# ThrusterShieldV1_1.net
KiCad netlist of a schematic drawn in EAGLE
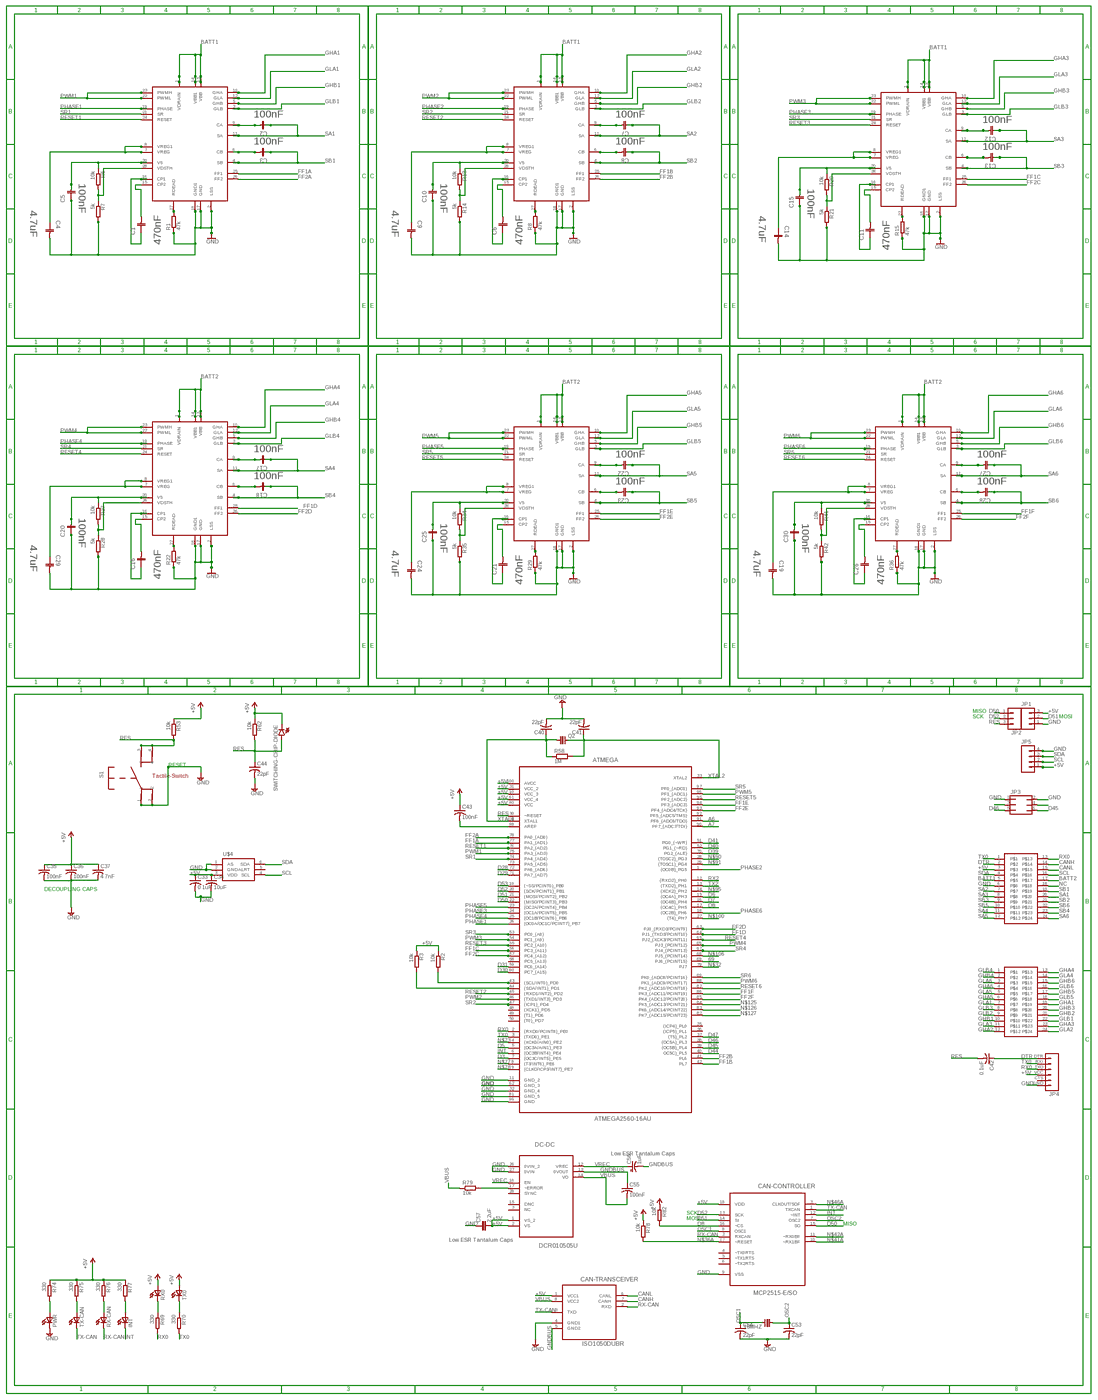
[diagram p0: schematic, sheet 1, overview]
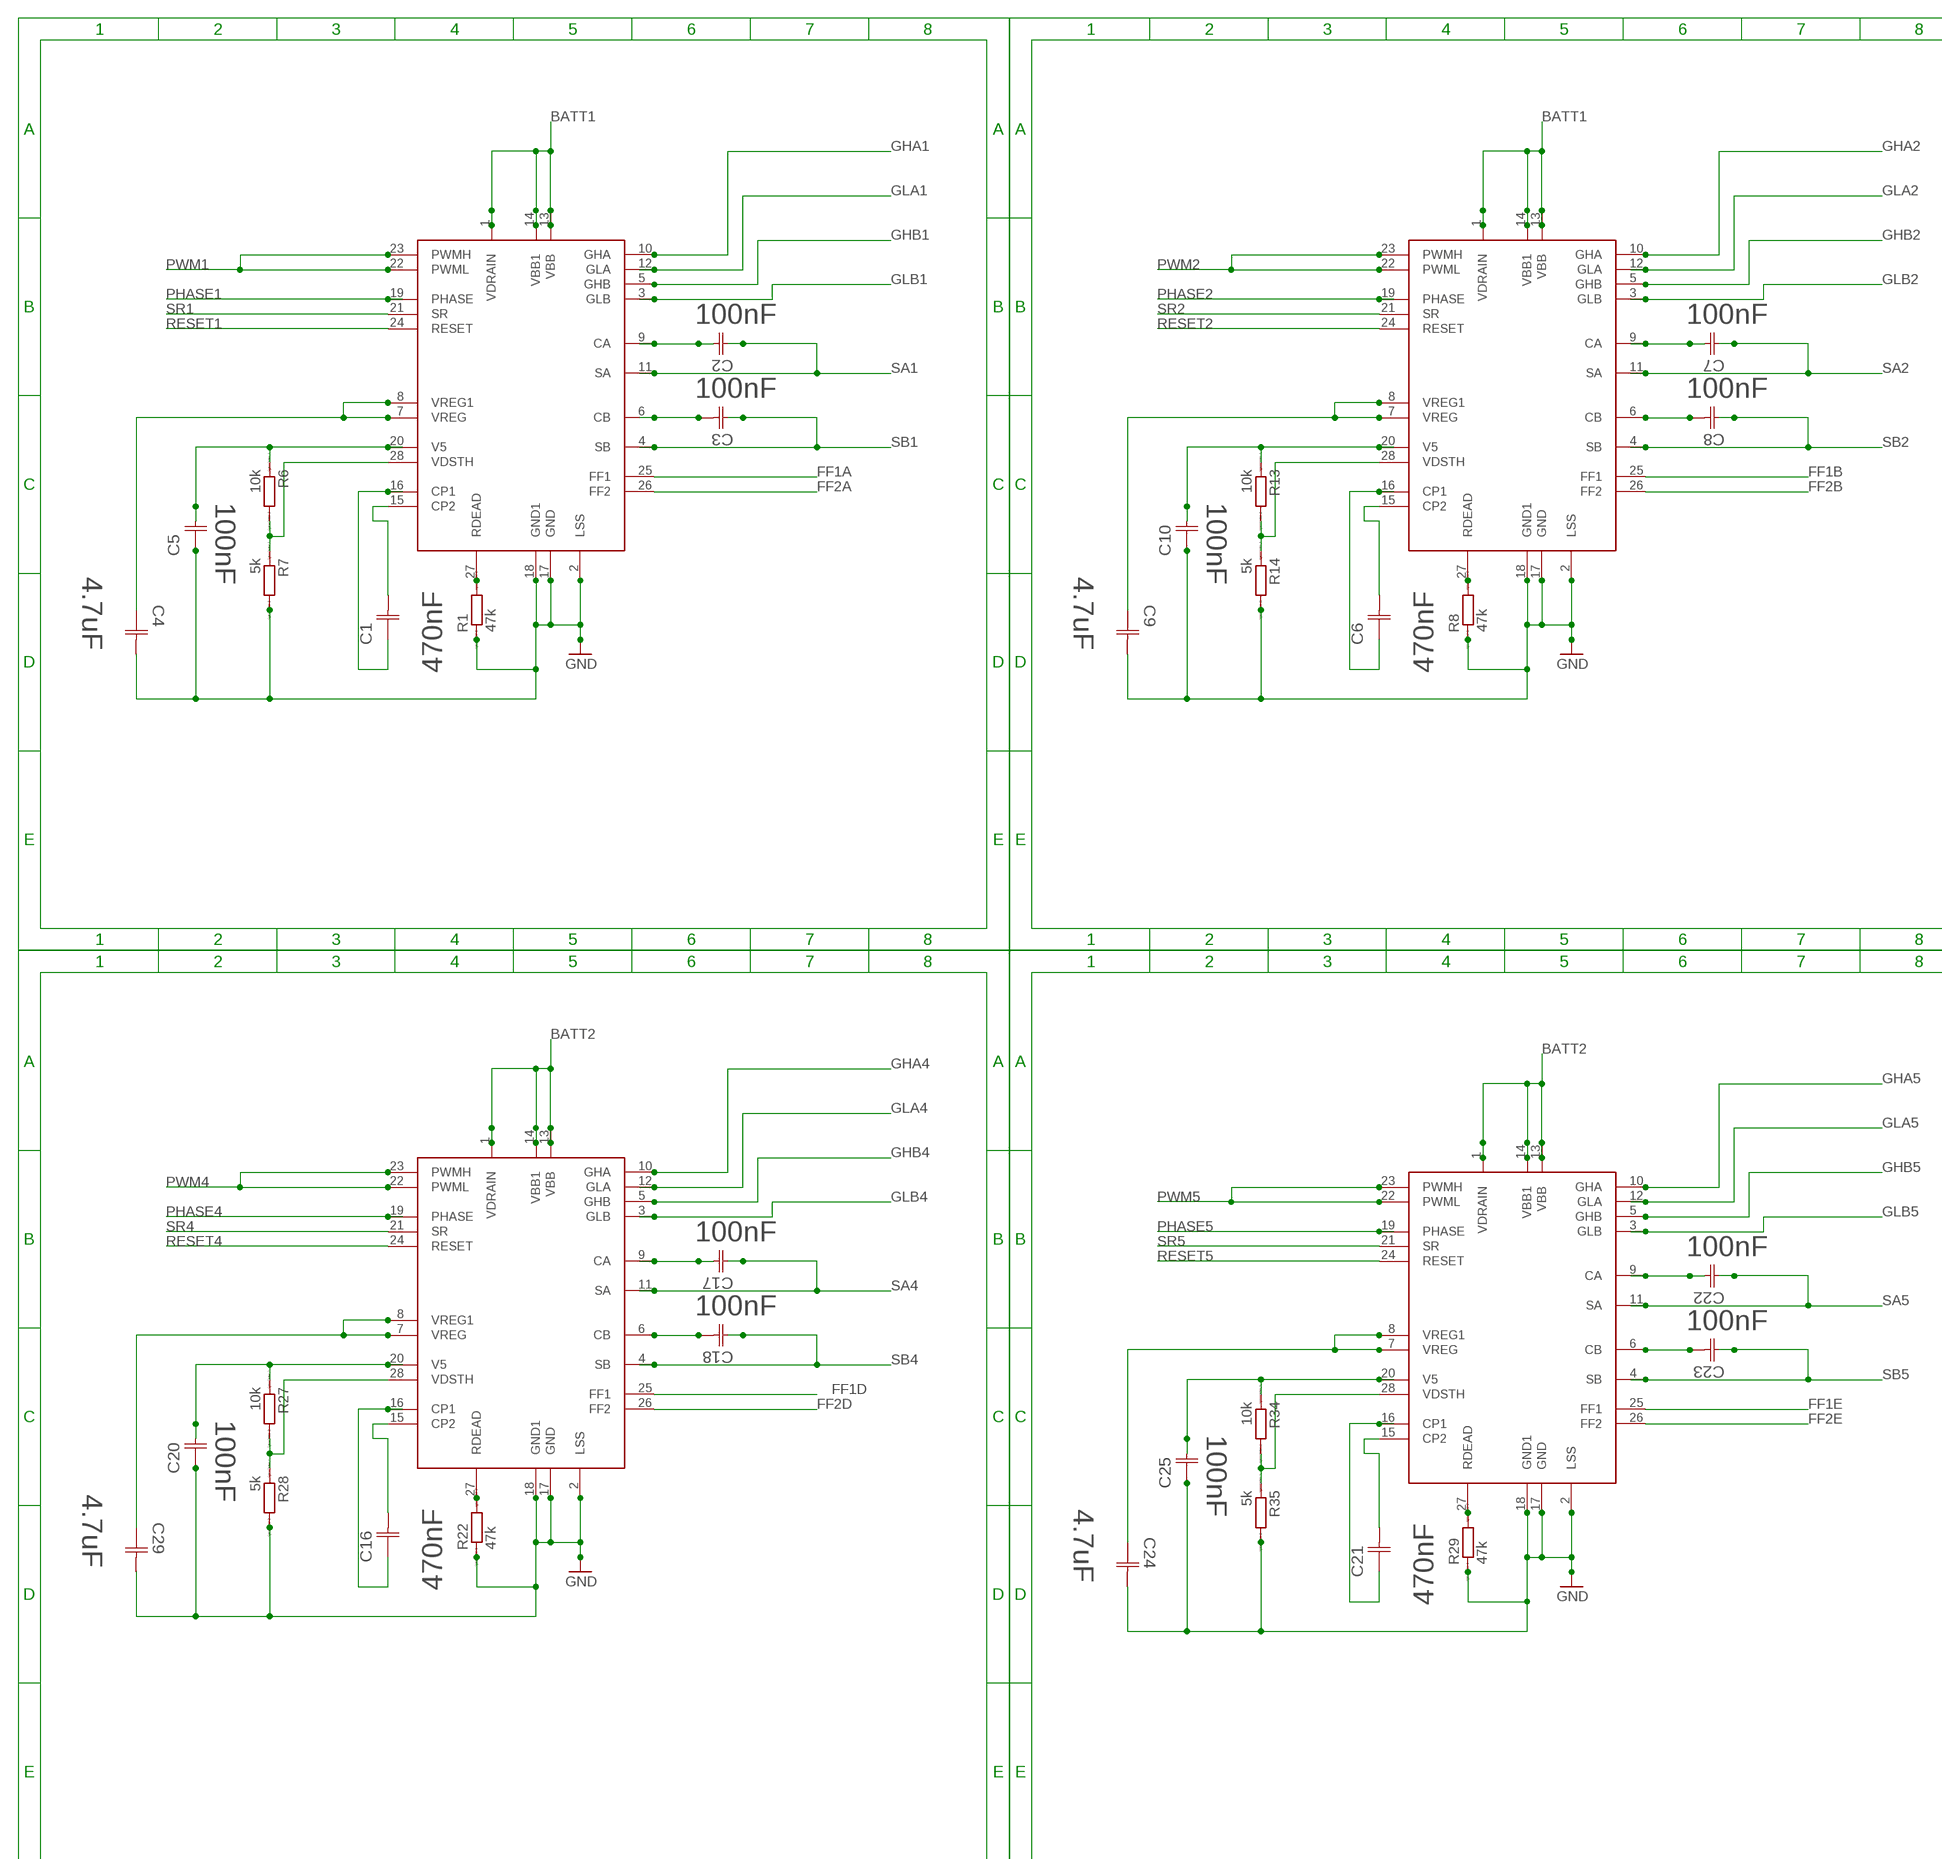
[diagram p1: schematic, sheet 1, part 1 of 4]
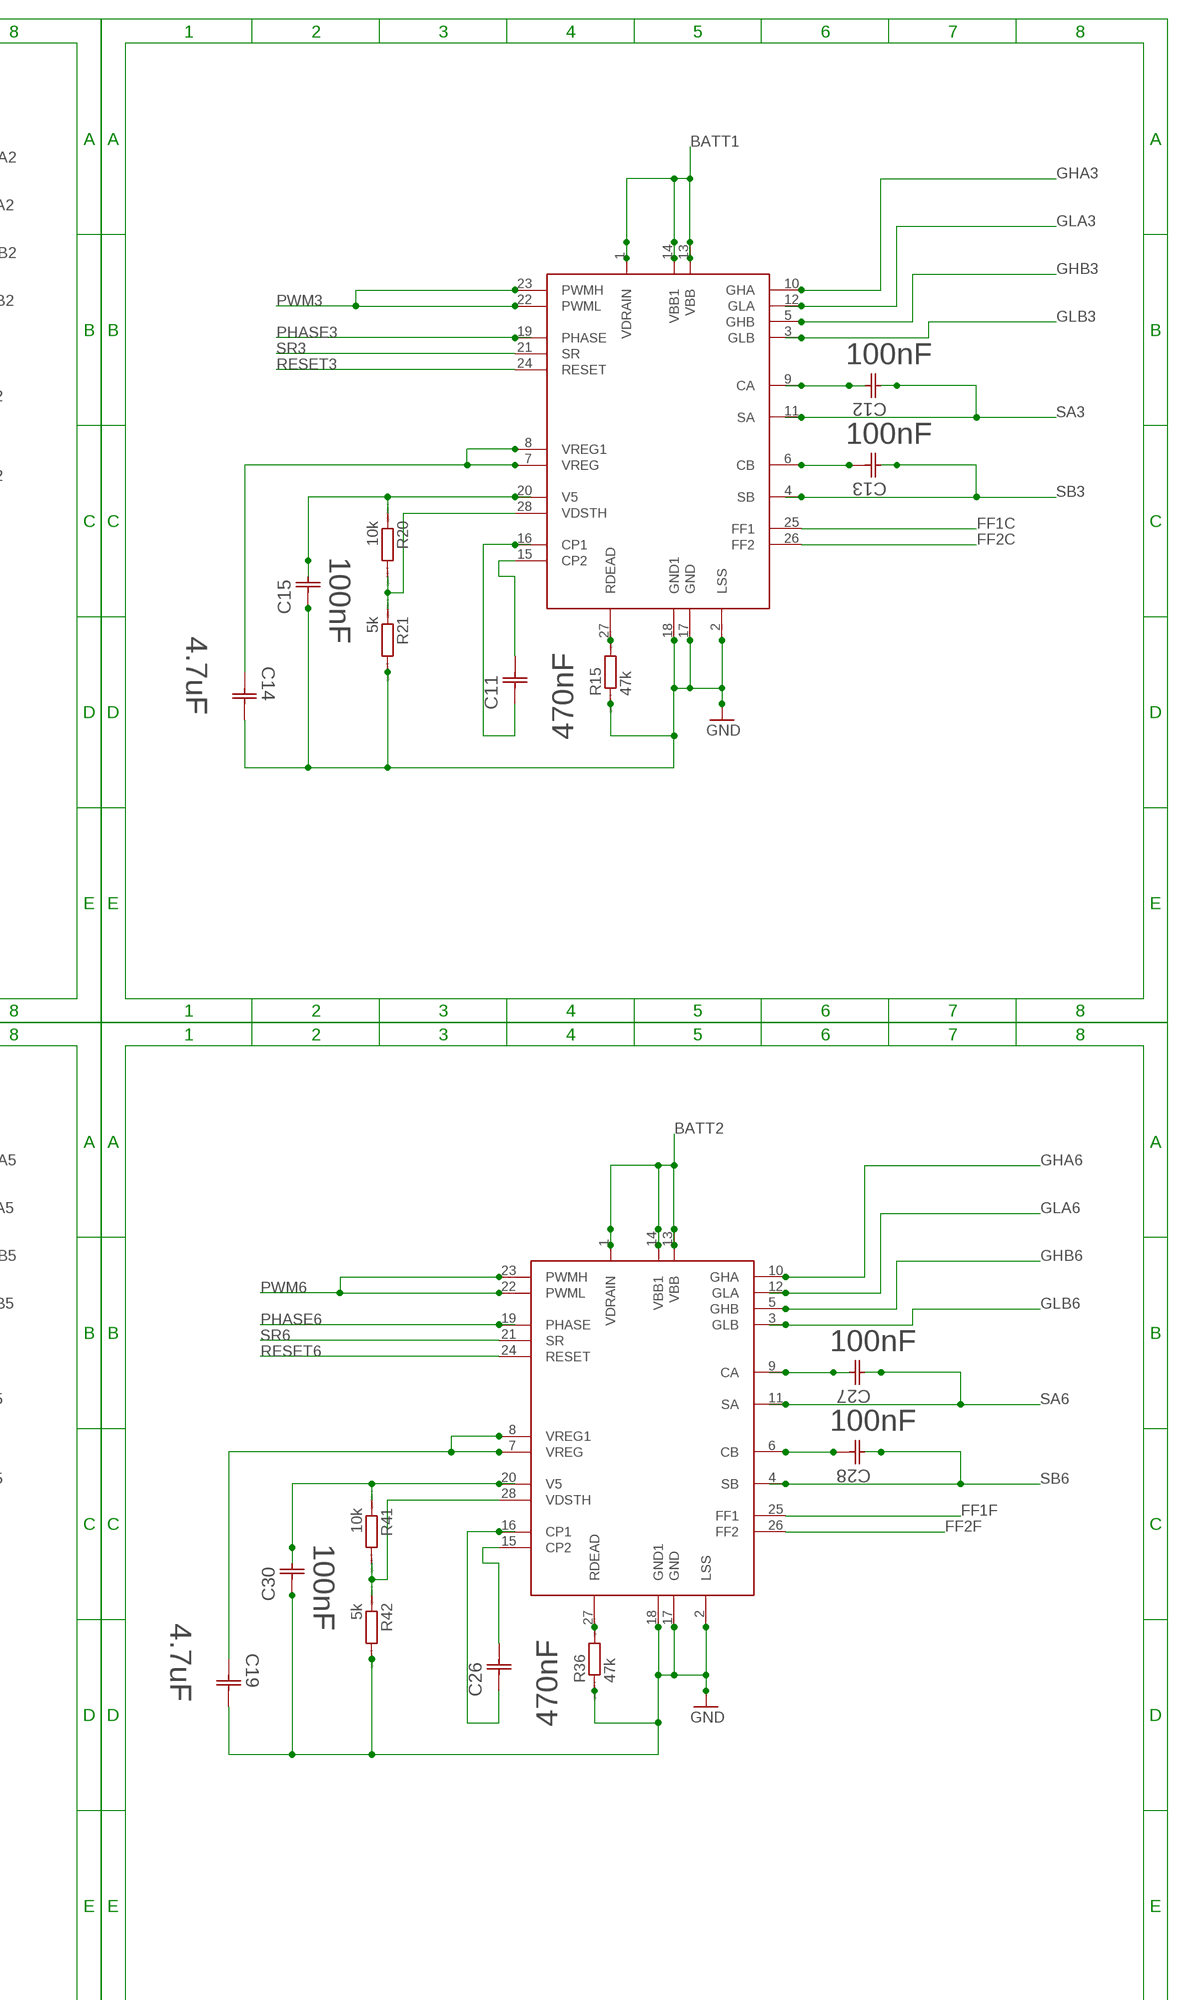
[diagram p2: schematic, sheet 1, part 2 of 4]
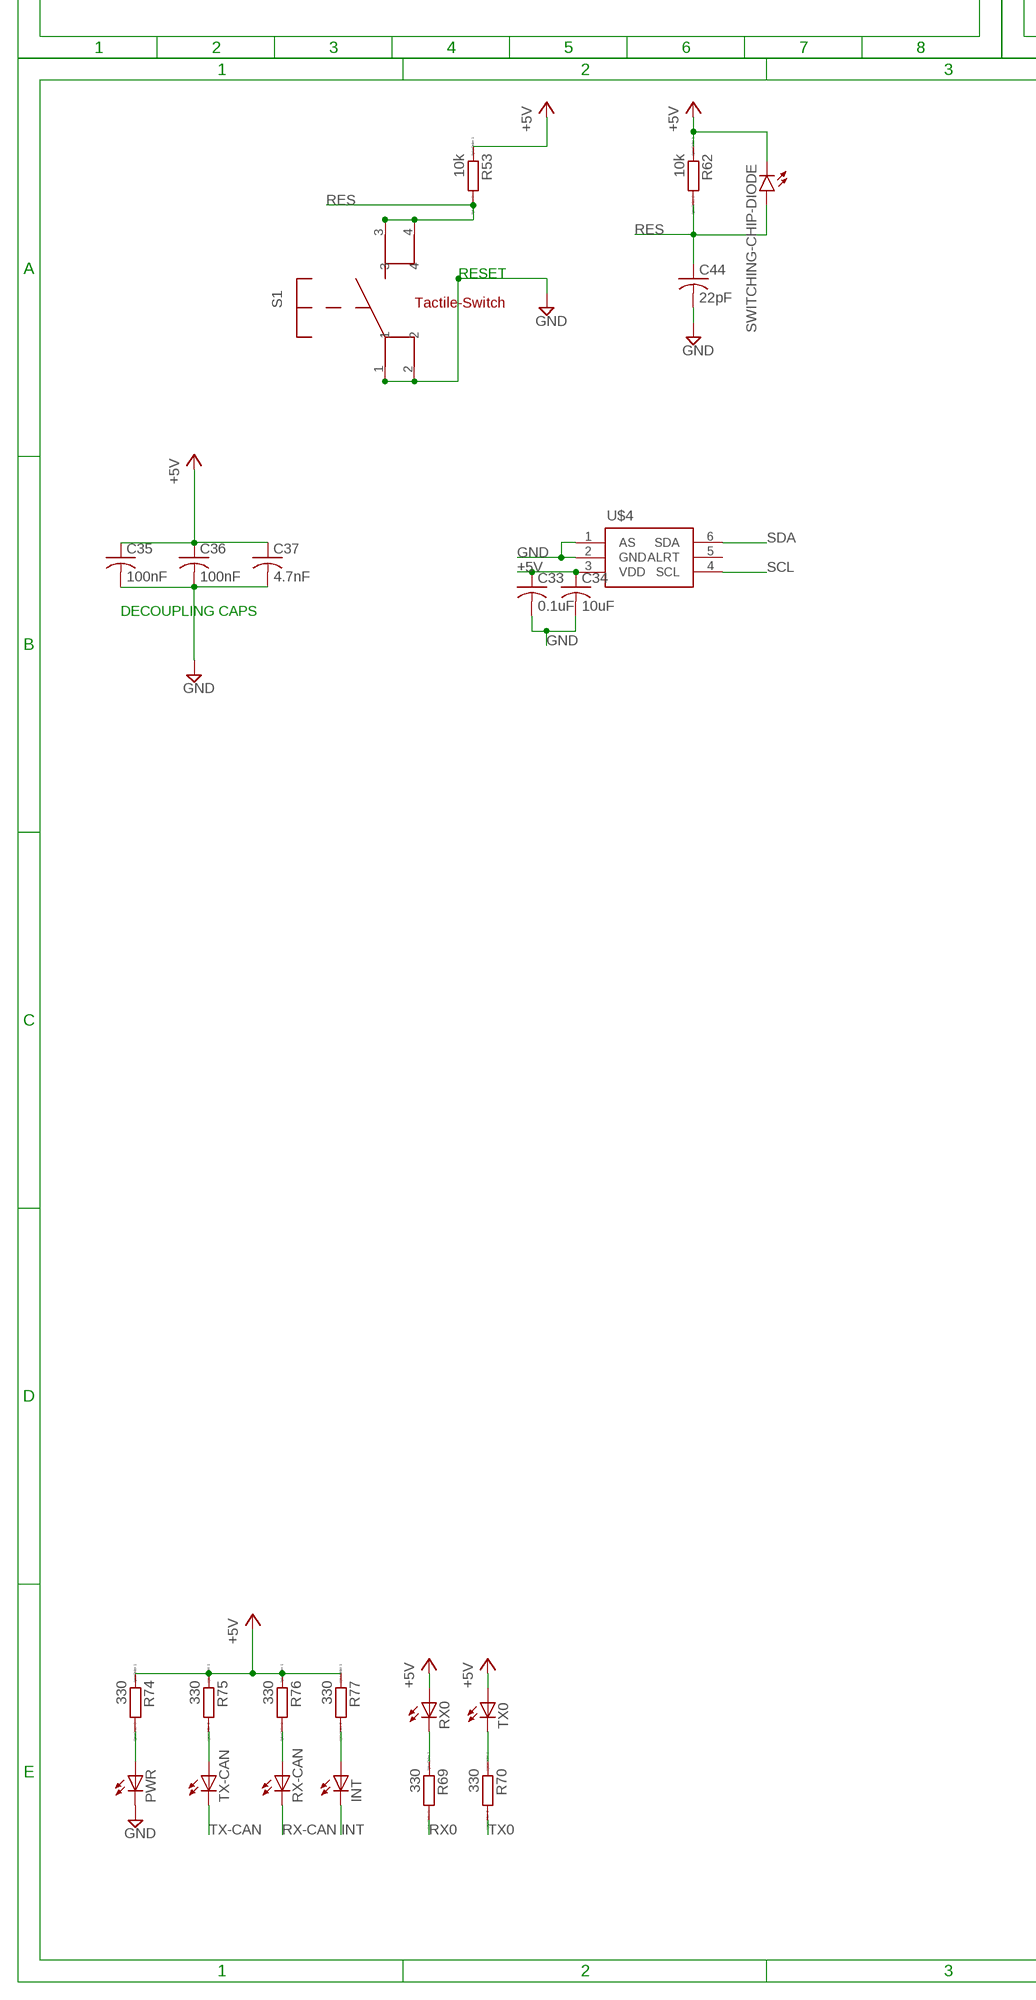
[diagram p3: schematic, sheet 1, part 3 of 4]
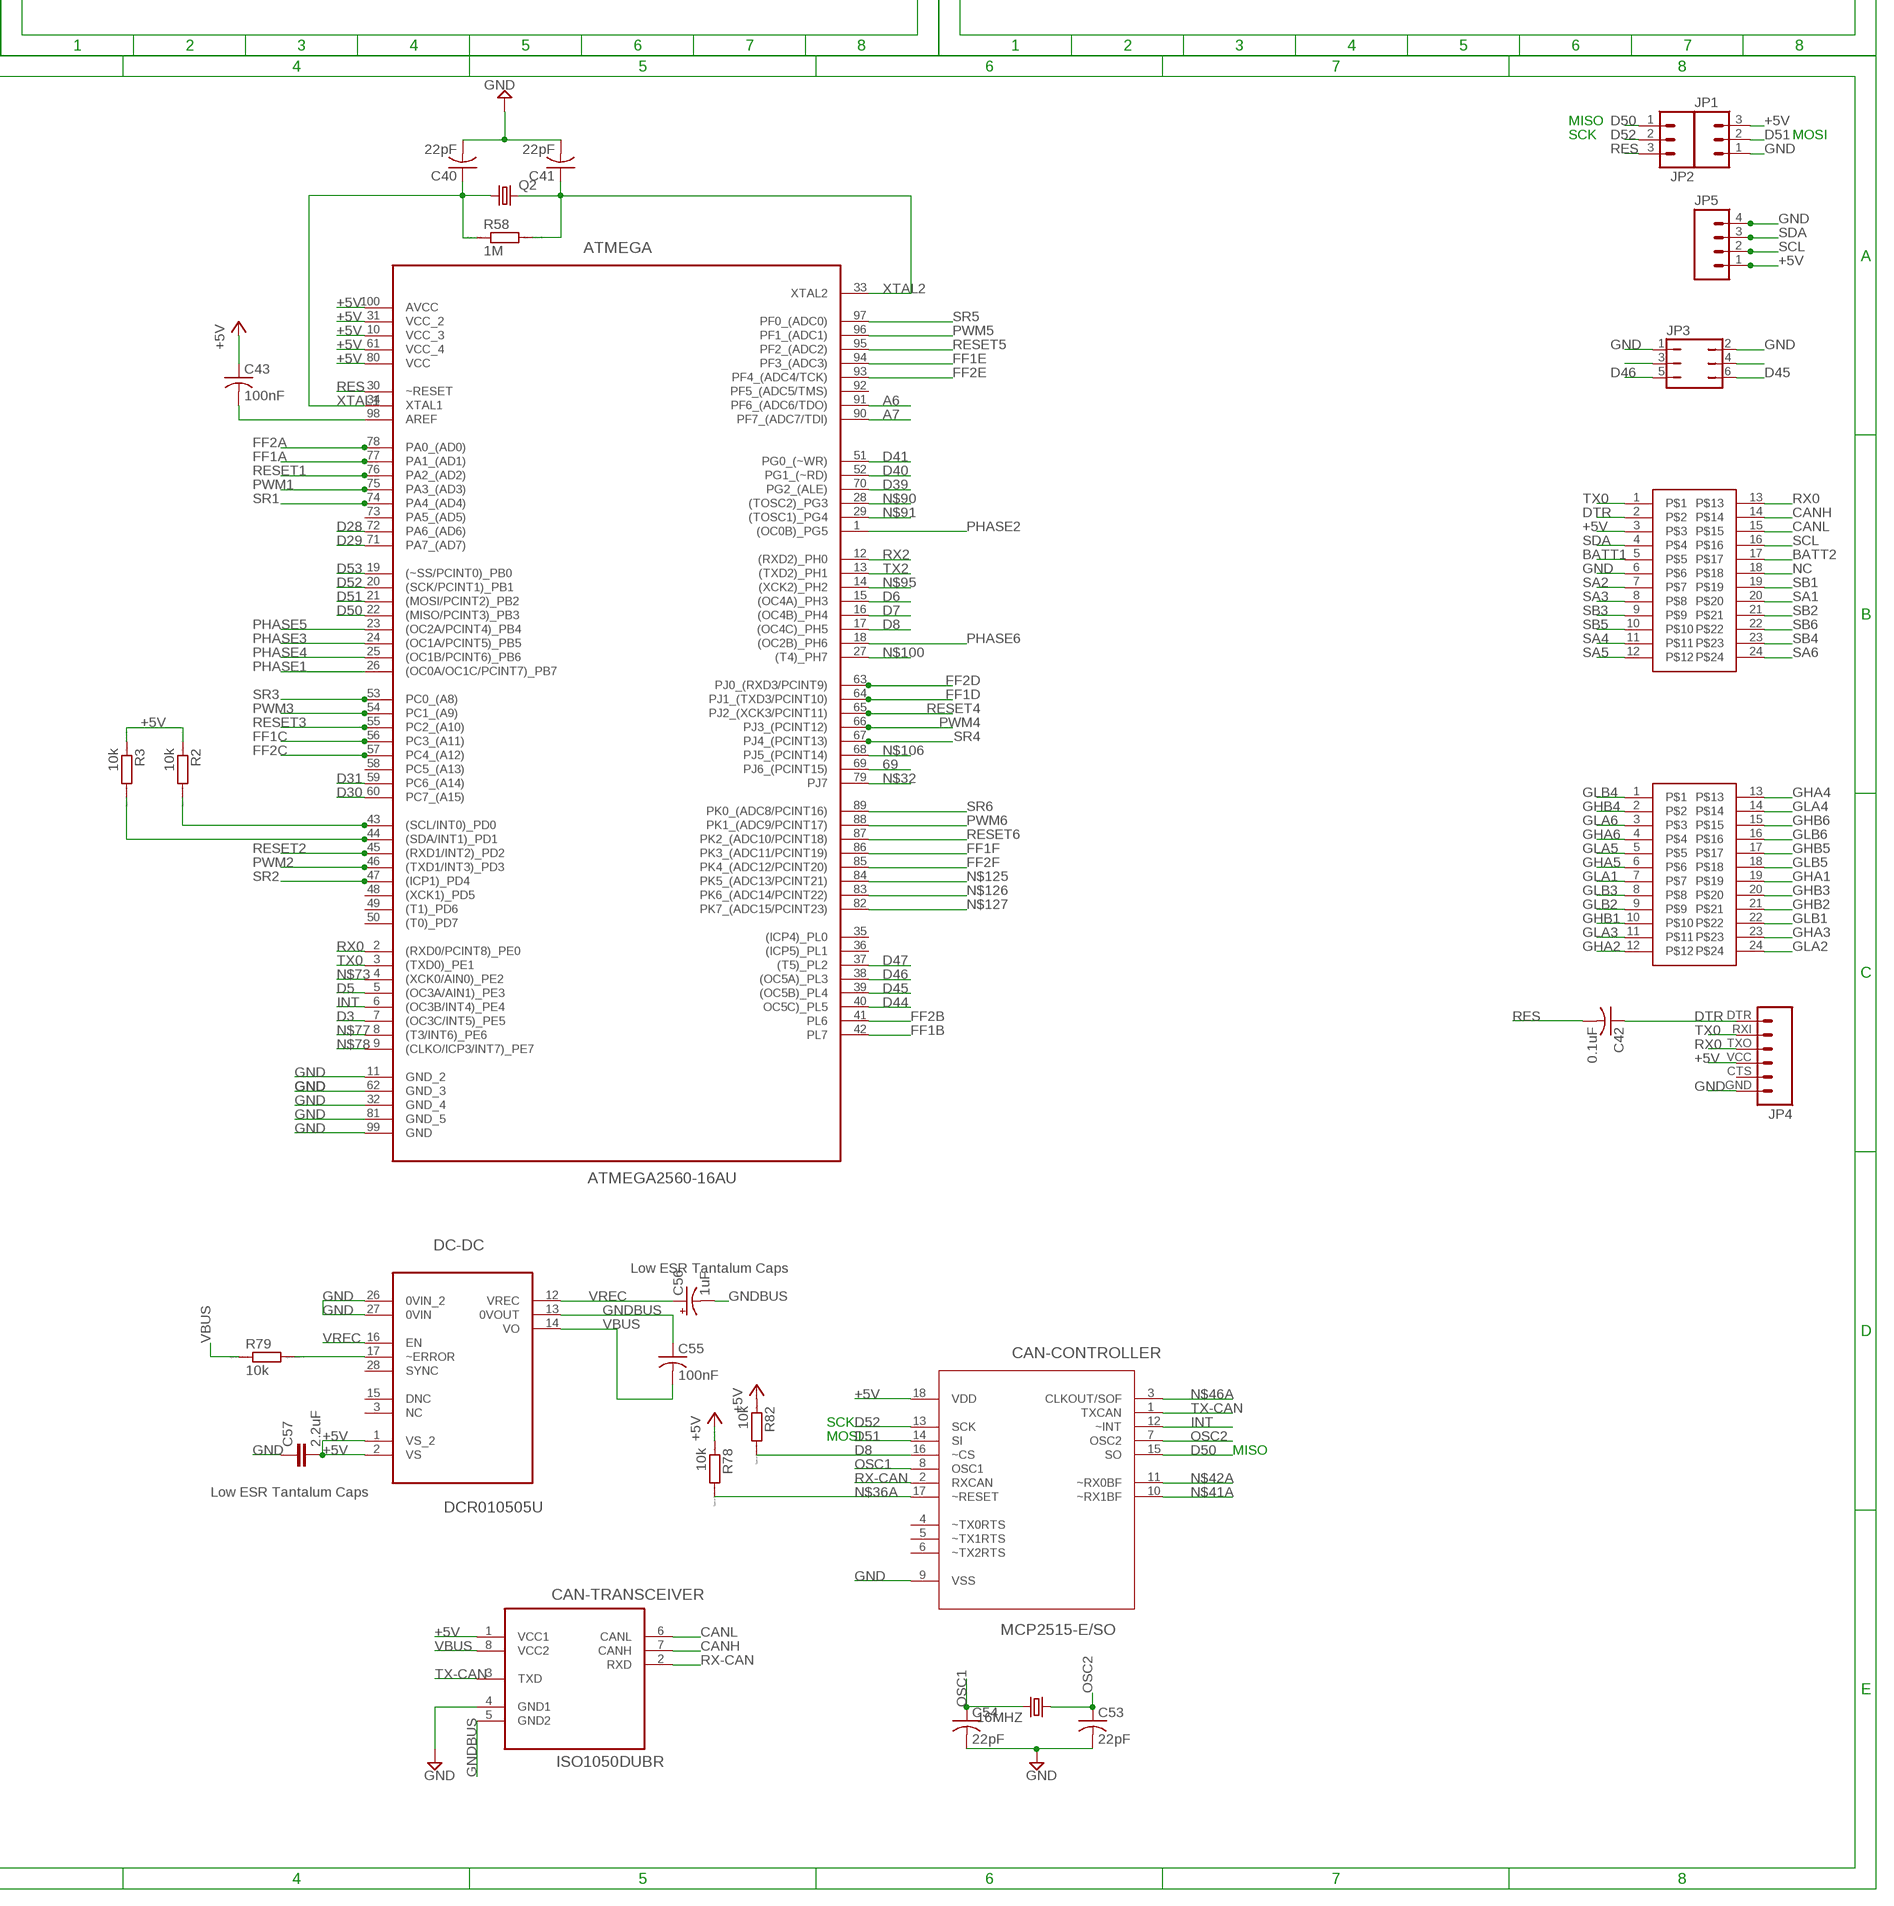
[diagram p4: schematic, sheet 1, part 4 of 4]

(export (version "E")
  (design (tool "Eeschema 10.0.6"))
  (components
    (comp (ref "16MHZ")
      (value "CRYSTALHC49UP")
      (footprint "eagle-import:HC49UP")
      (libsource (lib "eagle-import") (part "CRYSTALHC49UP"))
    )
    (comp (ref "ATMEGA")
      (value "ATMEGA2560-16AU")
      (footprint "eagle-import:QFP50P1600X1600X120-100N")
      (libsource (lib "eagle-import") (part "ATMEGA2560-16AU"))
    )
    (comp (ref "C1")
      (value "470nF")
      (footprint "eagle-import:CAPC2013X70N")
      (fields (field (name "MPN") "B37940K5100J60") (field (name "TOLERANCE") "±5%"))
      (libsource (lib "eagle-import") (part "B37940K5100J60"))
    )
    (comp (ref "C2")
      (value "100nF")
      (footprint "eagle-import:CAPC2013X70N")
      (fields (field (name "MPN") "B37940K5100J60") (field (name "TOLERANCE") "±5%"))
      (libsource (lib "eagle-import") (part "B37940K5100J60"))
    )
    (comp (ref "C3")
      (value "100nF")
      (footprint "eagle-import:CAPC2013X70N")
      (fields (field (name "MPN") "B37940K5100J60") (field (name "TOLERANCE") "±5%"))
      (libsource (lib "eagle-import") (part "B37940K5100J60"))
    )
    (comp (ref "C4")
      (value "4.7uF")
      (footprint "eagle-import:CAPC2013X70N")
      (fields (field (name "MPN") "B37940K5100J60") (field (name "TOLERANCE") "±5%"))
      (libsource (lib "eagle-import") (part "B37940K5100J60"))
    )
    (comp (ref "C5")
      (value "100nF")
      (footprint "eagle-import:CAPC2013X70N")
      (fields (field (name "MPN") "B37940K5100J60") (field (name "TOLERANCE") "±5%"))
      (libsource (lib "eagle-import") (part "B37940K5100J60"))
    )
    (comp (ref "C6")
      (value "470nF")
      (footprint "eagle-import:CAPC2013X70N")
      (fields (field (name "MPN") "B37940K5100J60") (field (name "TOLERANCE") "±5%"))
      (libsource (lib "eagle-import") (part "B37940K5100J60"))
    )
    (comp (ref "C7")
      (value "100nF")
      (footprint "eagle-import:CAPC2013X70N")
      (fields (field (name "MPN") "B37940K5100J60") (field (name "TOLERANCE") "±5%"))
      (libsource (lib "eagle-import") (part "B37940K5100J60"))
    )
    (comp (ref "C8")
      (value "100nF")
      (footprint "eagle-import:CAPC2013X70N")
      (fields (field (name "MPN") "B37940K5100J60") (field (name "TOLERANCE") "±5%"))
      (libsource (lib "eagle-import") (part "B37940K5100J60"))
    )
    (comp (ref "C9")
      (value "4.7uF")
      (footprint "eagle-import:CAPC2013X70N")
      (fields (field (name "MPN") "B37940K5100J60") (field (name "TOLERANCE") "±5%"))
      (libsource (lib "eagle-import") (part "B37940K5100J60"))
    )
    (comp (ref "C10")
      (value "100nF")
      (footprint "eagle-import:CAPC2013X70N")
      (fields (field (name "MPN") "B37940K5100J60") (field (name "TOLERANCE") "±5%"))
      (libsource (lib "eagle-import") (part "B37940K5100J60"))
    )
    (comp (ref "C11")
      (value "470nF")
      (footprint "eagle-import:CAPC2013X70N")
      (fields (field (name "MPN") "B37940K5100J60") (field (name "TOLERANCE") "±5%"))
      (libsource (lib "eagle-import") (part "B37940K5100J60"))
    )
    (comp (ref "C12")
      (value "100nF")
      (footprint "eagle-import:CAPC2013X70N")
      (fields (field (name "MPN") "B37940K5100J60") (field (name "TOLERANCE") "±5%"))
      (libsource (lib "eagle-import") (part "B37940K5100J60"))
    )
    (comp (ref "C13")
      (value "100nF")
      (footprint "eagle-import:CAPC2013X70N")
      (fields (field (name "MPN") "B37940K5100J60") (field (name "TOLERANCE") "±5%"))
      (libsource (lib "eagle-import") (part "B37940K5100J60"))
    )
    (comp (ref "C14")
      (value "4.7uF")
      (footprint "eagle-import:CAPC2013X70N")
      (fields (field (name "MPN") "B37940K5100J60") (field (name "TOLERANCE") "±5%"))
      (libsource (lib "eagle-import") (part "B37940K5100J60"))
    )
    (comp (ref "C15")
      (value "100nF")
      (footprint "eagle-import:CAPC2013X70N")
      (fields (field (name "MPN") "B37940K5100J60") (field (name "TOLERANCE") "±5%"))
      (libsource (lib "eagle-import") (part "B37940K5100J60"))
    )
    (comp (ref "C16")
      (value "470nF")
      (footprint "eagle-import:CAPC2013X70N")
      (fields (field (name "MPN") "B37940K5100J60") (field (name "TOLERANCE") "±5%"))
      (libsource (lib "eagle-import") (part "B37940K5100J60"))
    )
    (comp (ref "C17")
      (value "100nF")
      (footprint "eagle-import:CAPC2013X70N")
      (fields (field (name "MPN") "B37940K5100J60") (field (name "TOLERANCE") "±5%"))
      (libsource (lib "eagle-import") (part "B37940K5100J60"))
    )
    (comp (ref "C18")
      (value "100nF")
      (footprint "eagle-import:CAPC2013X70N")
      (fields (field (name "MPN") "B37940K5100J60") (field (name "TOLERANCE") "±5%"))
      (libsource (lib "eagle-import") (part "B37940K5100J60"))
    )
    (comp (ref "C19")
      (value "4.7uF")
      (footprint "eagle-import:CAPC2013X70N")
      (fields (field (name "MPN") "B37940K5100J60") (field (name "TOLERANCE") "±5%"))
      (libsource (lib "eagle-import") (part "B37940K5100J60"))
    )
    (comp (ref "C20")
      (value "100nF")
      (footprint "eagle-import:CAPC2013X70N")
      (fields (field (name "MPN") "B37940K5100J60") (field (name "TOLERANCE") "±5%"))
      (libsource (lib "eagle-import") (part "B37940K5100J60"))
    )
    (comp (ref "C21")
      (value "470nF")
      (footprint "eagle-import:CAPC2013X70N")
      (fields (field (name "MPN") "B37940K5100J60") (field (name "TOLERANCE") "±5%"))
      (libsource (lib "eagle-import") (part "B37940K5100J60"))
    )
    (comp (ref "C22")
      (value "100nF")
      (footprint "eagle-import:CAPC2013X70N")
      (fields (field (name "MPN") "B37940K5100J60") (field (name "TOLERANCE") "±5%"))
      (libsource (lib "eagle-import") (part "B37940K5100J60"))
    )
    (comp (ref "C23")
      (value "100nF")
      (footprint "eagle-import:CAPC2013X70N")
      (fields (field (name "MPN") "B37940K5100J60") (field (name "TOLERANCE") "±5%"))
      (libsource (lib "eagle-import") (part "B37940K5100J60"))
    )
    (comp (ref "C24")
      (value "4.7uF")
      (footprint "eagle-import:CAPC2013X70N")
      (fields (field (name "MPN") "B37940K5100J60") (field (name "TOLERANCE") "±5%"))
      (libsource (lib "eagle-import") (part "B37940K5100J60"))
    )
    (comp (ref "C25")
      (value "100nF")
      (footprint "eagle-import:CAPC2013X70N")
      (fields (field (name "MPN") "B37940K5100J60") (field (name "TOLERANCE") "±5%"))
      (libsource (lib "eagle-import") (part "B37940K5100J60"))
    )
    (comp (ref "C26")
      (value "470nF")
      (footprint "eagle-import:CAPC2013X70N")
      (fields (field (name "MPN") "B37940K5100J60") (field (name "TOLERANCE") "±5%"))
      (libsource (lib "eagle-import") (part "B37940K5100J60"))
    )
    (comp (ref "C27")
      (value "100nF")
      (footprint "eagle-import:CAPC2013X70N")
      (fields (field (name "MPN") "B37940K5100J60") (field (name "TOLERANCE") "±5%"))
      (libsource (lib "eagle-import") (part "B37940K5100J60"))
    )
    (comp (ref "C28")
      (value "100nF")
      (footprint "eagle-import:CAPC2013X70N")
      (fields (field (name "MPN") "B37940K5100J60") (field (name "TOLERANCE") "±5%"))
      (libsource (lib "eagle-import") (part "B37940K5100J60"))
    )
    (comp (ref "C29")
      (value "4.7uF")
      (footprint "eagle-import:CAPC2013X70N")
      (fields (field (name "MPN") "B37940K5100J60") (field (name "TOLERANCE") "±5%"))
      (libsource (lib "eagle-import") (part "B37940K5100J60"))
    )
    (comp (ref "C30")
      (value "100nF")
      (footprint "eagle-import:CAPC2013X70N")
      (fields (field (name "MPN") "B37940K5100J60") (field (name "TOLERANCE") "±5%"))
      (libsource (lib "eagle-import") (part "B37940K5100J60"))
    )
    (comp (ref "C33")
      (value "0.1uF")
      (footprint "eagle-import:C0805")
      (libsource (lib "eagle-import") (part "C-USC0805"))
    )
    (comp (ref "C34")
      (value "10uF")
      (footprint "eagle-import:C0805")
      (libsource (lib "eagle-import") (part "C-USC0805"))
    )
    (comp (ref "C35")
      (value "100nF")
      (footprint "eagle-import:C0805")
      (libsource (lib "eagle-import") (part "C-USC0805"))
    )
    (comp (ref "C36")
      (value "100nF")
      (footprint "eagle-import:C0805")
      (libsource (lib "eagle-import") (part "C-USC0805"))
    )
    (comp (ref "C37")
      (value "4.7nF")
      (footprint "eagle-import:C0805")
      (libsource (lib "eagle-import") (part "C-USC0805"))
    )
    (comp (ref "C40")
      (value "22pF")
      (footprint "eagle-import:C0805")
      (libsource (lib "eagle-import") (part "C-USC0805"))
    )
    (comp (ref "C41")
      (value "22pF")
      (footprint "eagle-import:C0805")
      (libsource (lib "eagle-import") (part "C-USC0805"))
    )
    (comp (ref "C42")
      (value "0.1uF")
      (footprint "eagle-import:C0805")
      (libsource (lib "eagle-import") (part "C-USC0805"))
    )
    (comp (ref "C43")
      (value "100nF")
      (footprint "eagle-import:C0805")
      (libsource (lib "eagle-import") (part "C-USC0805"))
    )
    (comp (ref "C44")
      (value "22pF")
      (footprint "eagle-import:C0805")
      (libsource (lib "eagle-import") (part "C-USC0805"))
    )
    (comp (ref "C53")
      (value "22pF")
      (footprint "eagle-import:C0805")
      (libsource (lib "eagle-import") (part "C-USC0805"))
    )
    (comp (ref "C54")
      (value "22pF")
      (footprint "eagle-import:C0805")
      (libsource (lib "eagle-import") (part "C-USC0805"))
    )
    (comp (ref "C55")
      (value "100nF")
      (footprint "eagle-import:C0805")
      (libsource (lib "eagle-import") (part "C-USC0805"))
    )
    (comp (ref "C56")
      (value "1uF")
      (footprint "eagle-import:EIA6032")
      (libsource (lib "eagle-import") (part "CAP_POL6032"))
    )
    (comp (ref "C57")
      (value "2.2uF")
      (footprint "eagle-import:0603-CAP")
      (libsource (lib "eagle-import") (part "CAP0603-CAP"))
    )
    (comp (ref "CAN-CONTROLLER")
      (value "MCP2515-E/SO")
      (footprint "eagle-import:SOIC127P1030X265-18N")
      (libsource (lib "eagle-import") (part "MCP2515-E/SO"))
    )
    (comp (ref "CAN-TRANSCEIVER")
      (value "ISO1050DUBR")
      (footprint "eagle-import:SOIC254P1040X485-8N")
      (libsource (lib "eagle-import") (part "ISO1050DUBR"))
    )
    (comp (ref "DC-DC")
      (value "DCR010505U")
      (footprint "eagle-import:SOIC127P1032X265-12NA")
      (libsource (lib "eagle-import") (part "DCR010505U"))
    )
    (comp (ref "INT")
      (value "LEDCHIP-LED0805")
      (footprint "eagle-import:CHIP-LED0805")
      (libsource (lib "eagle-import") (part "LEDCHIP-LED0805"))
    )
    (comp (ref "JP1")
      (value "M03LOCK")
      (footprint "eagle-import:1X03_LOCK")
      (libsource (lib "eagle-import") (part "M03LOCK"))
    )
    (comp (ref "JP2")
      (value "M03LOCK")
      (footprint "eagle-import:1X03_LOCK")
      (libsource (lib "eagle-import") (part "M03LOCK"))
    )
    (comp (ref "JP3")
      (value "JP3Q")
      (footprint "eagle-import:JP3Q")
      (libsource (lib "eagle-import") (part "JP3Q"))
    )
    (comp (ref "JP4")
      (value "M06SIP")
      (footprint "eagle-import:1X06")
      (libsource (lib "eagle-import") (part "M06SIP"))
    )
    (comp (ref "JP5")
      (value "M04PTH")
      (footprint "eagle-import:1X04")
      (libsource (lib "eagle-import") (part "M04PTH"))
    )
    (comp (ref "PWR")
      (value "LEDCHIP-LED0805")
      (footprint "eagle-import:CHIP-LED0805")
      (libsource (lib "eagle-import") (part "LEDCHIP-LED0805"))
    )
    (comp (ref "Q2")
      (value "CRYSTALHC49UP")
      (footprint "eagle-import:HC49UP")
      (libsource (lib "eagle-import") (part "CRYSTALHC49UP"))
    )
    (comp (ref "R1")
      (value "47k")
      (footprint "eagle-import:R0805")
      (libsource (lib "eagle-import") (part "R"))
    )
    (comp (ref "R2")
      (value "10k")
      (footprint "eagle-import:R0805")
      (libsource (lib "eagle-import") (part "R"))
    )
    (comp (ref "R3")
      (value "10k")
      (footprint "eagle-import:R0805")
      (libsource (lib "eagle-import") (part "R"))
    )
    (comp (ref "R6")
      (value "10k")
      (footprint "eagle-import:R0805")
      (libsource (lib "eagle-import") (part "R"))
    )
    (comp (ref "R7")
      (value "5k")
      (footprint "eagle-import:R0805")
      (libsource (lib "eagle-import") (part "R"))
    )
    (comp (ref "R8")
      (value "47k")
      (footprint "eagle-import:R0805")
      (libsource (lib "eagle-import") (part "R"))
    )
    (comp (ref "R13")
      (value "10k")
      (footprint "eagle-import:R0805")
      (libsource (lib "eagle-import") (part "R"))
    )
    (comp (ref "R14")
      (value "5k")
      (footprint "eagle-import:R0805")
      (libsource (lib "eagle-import") (part "R"))
    )
    (comp (ref "R15")
      (value "47k")
      (footprint "eagle-import:R0805")
      (libsource (lib "eagle-import") (part "R"))
    )
    (comp (ref "R20")
      (value "10k")
      (footprint "eagle-import:R0805")
      (libsource (lib "eagle-import") (part "R"))
    )
    (comp (ref "R21")
      (value "5k")
      (footprint "eagle-import:R0805")
      (libsource (lib "eagle-import") (part "R"))
    )
    (comp (ref "R22")
      (value "47k")
      (footprint "eagle-import:R0805")
      (libsource (lib "eagle-import") (part "R"))
    )
    (comp (ref "R27")
      (value "10k")
      (footprint "eagle-import:R0805")
      (libsource (lib "eagle-import") (part "R"))
    )
    (comp (ref "R28")
      (value "5k")
      (footprint "eagle-import:R0805")
      (libsource (lib "eagle-import") (part "R"))
    )
    (comp (ref "R29")
      (value "47k")
      (footprint "eagle-import:R0805")
      (libsource (lib "eagle-import") (part "R"))
    )
    (comp (ref "R34")
      (value "10k")
      (footprint "eagle-import:R0805")
      (libsource (lib "eagle-import") (part "R"))
    )
    (comp (ref "R35")
      (value "5k")
      (footprint "eagle-import:R0805")
      (libsource (lib "eagle-import") (part "R"))
    )
    (comp (ref "R36")
      (value "47k")
      (footprint "eagle-import:R0805")
      (libsource (lib "eagle-import") (part "R"))
    )
    (comp (ref "R41")
      (value "10k")
      (footprint "eagle-import:R0805")
      (libsource (lib "eagle-import") (part "R"))
    )
    (comp (ref "R42")
      (value "5k")
      (footprint "eagle-import:R0805")
      (libsource (lib "eagle-import") (part "R"))
    )
    (comp (ref "R53")
      (value "10k")
      (footprint "eagle-import:R0805")
      (libsource (lib "eagle-import") (part "R"))
    )
    (comp (ref "R58")
      (value "1M")
      (footprint "eagle-import:R0805")
      (libsource (lib "eagle-import") (part "R"))
    )
    (comp (ref "R62")
      (value "10k")
      (footprint "eagle-import:R0805")
      (libsource (lib "eagle-import") (part "R"))
    )
    (comp (ref "R69")
      (value "330")
      (footprint "eagle-import:R0805")
      (libsource (lib "eagle-import") (part "R"))
    )
    (comp (ref "R70")
      (value "330")
      (footprint "eagle-import:R0805")
      (libsource (lib "eagle-import") (part "R"))
    )
    (comp (ref "R74")
      (value "330")
      (footprint "eagle-import:R0805")
      (libsource (lib "eagle-import") (part "R"))
    )
    (comp (ref "R75")
      (value "330")
      (footprint "eagle-import:R0805")
      (libsource (lib "eagle-import") (part "R"))
    )
    (comp (ref "R76")
      (value "330")
      (footprint "eagle-import:R0805")
      (libsource (lib "eagle-import") (part "R"))
    )
    (comp (ref "R77")
      (value "330")
      (footprint "eagle-import:R0805")
      (libsource (lib "eagle-import") (part "R"))
    )
    (comp (ref "R78")
      (value "10k")
      (footprint "eagle-import:R0805")
      (libsource (lib "eagle-import") (part "R"))
    )
    (comp (ref "R79")
      (value "10k")
      (footprint "eagle-import:R0805")
      (libsource (lib "eagle-import") (part "R"))
    )
    (comp (ref "R82")
      (value "10k")
      (footprint "eagle-import:R0805")
      (libsource (lib "eagle-import") (part "R"))
    )
    (comp (ref "RX-CAN")
      (value "LEDCHIP-LED0805")
      (footprint "eagle-import:CHIP-LED0805")
      (libsource (lib "eagle-import") (part "LEDCHIP-LED0805"))
    )
    (comp (ref "RX0")
      (value "LEDCHIP-LED0805")
      (footprint "eagle-import:CHIP-LED0805")
      (libsource (lib "eagle-import") (part "LEDCHIP-LED0805"))
    )
    (comp (ref "SWITCHING-CHIP-DIODE")
      (value "LED1206")
      (footprint "eagle-import:LED-1206")
      (libsource (lib "eagle-import") (part "LED1206"))
    )
    (comp (ref "TX-CAN")
      (value "LEDCHIP-LED0805")
      (footprint "eagle-import:CHIP-LED0805")
      (libsource (lib "eagle-import") (part "LEDCHIP-LED0805"))
    )
    (comp (ref "TX0")
      (value "LEDCHIP-LED0805")
      (footprint "eagle-import:CHIP-LED0805")
      (libsource (lib "eagle-import") (part "LEDCHIP-LED0805"))
    )
    (comp (ref "U$1")
      (value "15-91-0360")
      (footprint "eagle-import:15-91-0360")
      (libsource (lib "eagle-import") (part "15-91-0360"))
    )
    (comp (ref "U$2")
      (value "15-91-0360")
      (footprint "eagle-import:15-91-0360")
      (libsource (lib "eagle-import") (part "15-91-0360"))
    )
    (comp (ref "U$4")
      (value "AD7414")
      (footprint "eagle-import:SOT23-6")
      (libsource (lib "eagle-import") (part "AD7414"))
    )
    (comp (ref "U$25")
      (value "A3941KLPTR-T")
      (footprint "eagle-import:TSSOP-28")
      (libsource (lib "eagle-import") (part "A3941KLPTR-T"))
    )
    (comp (ref "U$26")
      (value "A3941KLPTR-T")
      (footprint "eagle-import:TSSOP-28")
      (libsource (lib "eagle-import") (part "A3941KLPTR-T"))
    )
    (comp (ref "U$27")
      (value "A3941KLPTR-T")
      (footprint "eagle-import:TSSOP-28")
      (libsource (lib "eagle-import") (part "A3941KLPTR-T"))
    )
    (comp (ref "U$28")
      (value "A3941KLPTR-T")
      (footprint "eagle-import:TSSOP-28")
      (libsource (lib "eagle-import") (part "A3941KLPTR-T"))
    )
    (comp (ref "U$29")
      (value "A3941KLPTR-T")
      (footprint "eagle-import:TSSOP-28")
      (libsource (lib "eagle-import") (part "A3941KLPTR-T"))
    )
    (comp (ref "U$30")
      (value "A3941KLPTR-T")
      (footprint "eagle-import:TSSOP-28")
      (libsource (lib "eagle-import") (part "A3941KLPTR-T"))
    )
    (comp (ref "U$35")
      (value "B3FS-1000")
      (footprint "eagle-import:B3F2-1000")
      (libsource (lib "eagle-import") (part "B3FS-1000"))
    )
  )
  (nets
    (net (code "1") (name "+5V") (class "Default")
      (node (ref "ATMEGA") (pin "10") (pinfunction "VCC_3_10") (pintype "power_in"))
      (node (ref "ATMEGA") (pin "100") (pinfunction "AVCC_100") (pintype "power_in"))
      (node (ref "ATMEGA") (pin "31") (pinfunction "VCC_2_31") (pintype "power_in"))
      (node (ref "ATMEGA") (pin "61") (pinfunction "VCC_4_61") (pintype "power_in"))
      (node (ref "ATMEGA") (pin "80") (pinfunction "VCC_80") (pintype "power_in"))
      (node (ref "C33") (pin "1") (pinfunction "1_1") (pintype "passive"))
      (node (ref "C34") (pin "1") (pinfunction "1_1") (pintype "passive"))
      (node (ref "C35") (pin "1") (pinfunction "1_1") (pintype "passive"))
      (node (ref "C36") (pin "1") (pinfunction "1_1") (pintype "passive"))
      (node (ref "C37") (pin "1") (pinfunction "1_1") (pintype "passive"))
      (node (ref "C43") (pin "1") (pinfunction "1_1") (pintype "passive"))
      (node (ref "C57") (pin "2") (pinfunction "2_2") (pintype "passive"))
      (node (ref "CAN-CONTROLLER") (pin "18") (pinfunction "VDD_18") (pintype "power_in"))
      (node (ref "CAN-TRANSCEIVER") (pin "1") (pinfunction "VCC1_1") (pintype "power_in"))
      (node (ref "DC-DC") (pin "1") (pinfunction "VS_2_1") (pintype "power_in"))
      (node (ref "DC-DC") (pin "2") (pinfunction "VS_2") (pintype "power_in"))
      (node (ref "JP1") (pin "3") (pinfunction "3_3") (pintype "passive"))
      (node (ref "JP4") (pin "VCC") (pinfunction "4_VCC") (pintype "passive"))
      (node (ref "JP5") (pin "1") (pinfunction "1_1") (pintype "passive"))
      (node (ref "R2") (pin "1") (pinfunction "1_1") (pintype "passive"))
      (node (ref "R3") (pin "1") (pinfunction "1_1") (pintype "passive"))
      (node (ref "R53") (pin "1") (pinfunction "1_1") (pintype "passive"))
      (node (ref "R62") (pin "1") (pinfunction "1_1") (pintype "passive"))
      (node (ref "R74") (pin "1") (pinfunction "1_1") (pintype "passive"))
      (node (ref "R75") (pin "1") (pinfunction "1_1") (pintype "passive"))
      (node (ref "R76") (pin "1") (pinfunction "1_1") (pintype "passive"))
      (node (ref "R77") (pin "1") (pinfunction "1_1") (pintype "passive"))
      (node (ref "R78") (pin "1") (pinfunction "1_1") (pintype "passive"))
      (node (ref "R82") (pin "1") (pinfunction "1_1") (pintype "passive"))
      (node (ref "RX0") (pin "A") (pinfunction "A_A") (pintype "passive"))
      (node (ref "SWITCHING-CHIP-DIODE") (pin "C") (pinfunction "C_C") (pintype "passive"))
      (node (ref "TX0") (pin "A") (pinfunction "A_A") (pintype "passive"))
      (node (ref "U$1") (pin "3") (pinfunction "P$3_3") (pintype "bidirectional"))
      (node (ref "U$4") (pin "3") (pinfunction "VDD_3") (pintype "bidirectional"))
    )
    (net (code "2") (name "/69") (class "Default")
      (node (ref "ATMEGA") (pin "69") (pinfunction "PJ6_(PCINT15)_69") (pintype "bidirectional"))
    )
    (net (code "3") (name "/A6") (class "Default")
      (node (ref "ATMEGA") (pin "91") (pinfunction "PF6_(ADC6/TDO)_91") (pintype "bidirectional"))
    )
    (net (code "4") (name "/A7") (class "Default")
      (node (ref "ATMEGA") (pin "90") (pinfunction "PF7_(ADC7/TDI)_90") (pintype "bidirectional"))
    )
    (net (code "5") (name "/BATT1") (class "Default")
      (node (ref "U$1") (pin "5") (pinfunction "P$5_5") (pintype "bidirectional"))
      (node (ref "U$25") (pin "1") (pinfunction "VDRAIN_1") (pintype "power_in"))
      (node (ref "U$25") (pin "13") (pinfunction "VBB_13") (pintype "power_in"))
      (node (ref "U$25") (pin "14") (pinfunction "VBB1_14") (pintype "power_in"))
      (node (ref "U$26") (pin "1") (pinfunction "VDRAIN_1") (pintype "power_in"))
      (node (ref "U$26") (pin "13") (pinfunction "VBB_13") (pintype "power_in"))
      (node (ref "U$26") (pin "14") (pinfunction "VBB1_14") (pintype "power_in"))
      (node (ref "U$27") (pin "1") (pinfunction "VDRAIN_1") (pintype "power_in"))
      (node (ref "U$27") (pin "13") (pinfunction "VBB_13") (pintype "power_in"))
      (node (ref "U$27") (pin "14") (pinfunction "VBB1_14") (pintype "power_in"))
    )
    (net (code "6") (name "/BATT2") (class "Default")
      (node (ref "U$1") (pin "17") (pinfunction "P$17_17") (pintype "bidirectional"))
      (node (ref "U$28") (pin "1") (pinfunction "VDRAIN_1") (pintype "power_in"))
      (node (ref "U$28") (pin "13") (pinfunction "VBB_13") (pintype "power_in"))
      (node (ref "U$28") (pin "14") (pinfunction "VBB1_14") (pintype "power_in"))
      (node (ref "U$29") (pin "1") (pinfunction "VDRAIN_1") (pintype "power_in"))
      (node (ref "U$29") (pin "13") (pinfunction "VBB_13") (pintype "power_in"))
      (node (ref "U$29") (pin "14") (pinfunction "VBB1_14") (pintype "power_in"))
      (node (ref "U$30") (pin "1") (pinfunction "VDRAIN_1") (pintype "power_in"))
      (node (ref "U$30") (pin "13") (pinfunction "VBB_13") (pintype "power_in"))
      (node (ref "U$30") (pin "14") (pinfunction "VBB1_14") (pintype "power_in"))
    )
    (net (code "7") (name "/CANH") (class "Default")
      (node (ref "CAN-TRANSCEIVER") (pin "7") (pinfunction "CANH_7") (pintype "bidirectional"))
      (node (ref "U$1") (pin "14") (pinfunction "P$14_14") (pintype "bidirectional"))
    )
    (net (code "8") (name "/CANL") (class "Default")
      (node (ref "CAN-TRANSCEIVER") (pin "6") (pinfunction "CANL_6") (pintype "bidirectional"))
      (node (ref "U$1") (pin "15") (pinfunction "P$15_15") (pintype "bidirectional"))
    )
    (net (code "9") (name "/D3") (class "Default")
      (node (ref "ATMEGA") (pin "7") (pinfunction "(OC3C/INT5)_PE5_7") (pintype "bidirectional"))
    )
    (net (code "10") (name "/D5") (class "Default")
      (node (ref "ATMEGA") (pin "5") (pinfunction "(OC3A/AIN1)_PE3_5") (pintype "bidirectional"))
    )
    (net (code "11") (name "/D6") (class "Default")
      (node (ref "ATMEGA") (pin "15") (pinfunction "(OC4A)_PH3_15") (pintype "bidirectional"))
    )
    (net (code "12") (name "/D7") (class "Default")
      (node (ref "ATMEGA") (pin "16") (pinfunction "(OC4B)_PH4_16") (pintype "bidirectional"))
    )
    (net (code "13") (name "/D8") (class "Default")
      (node (ref "ATMEGA") (pin "17") (pinfunction "(OC4C)_PH5_17") (pintype "bidirectional"))
      (node (ref "CAN-CONTROLLER") (pin "16") (pinfunction "~{CS}_16") (pintype "input"))
      (node (ref "R82") (pin "2") (pinfunction "2_2") (pintype "passive"))
    )
    (net (code "14") (name "/D28") (class "Default")
      (node (ref "ATMEGA") (pin "72") (pinfunction "PA6_(AD6)_72") (pintype "bidirectional"))
    )
    (net (code "15") (name "/D29") (class "Default")
      (node (ref "ATMEGA") (pin "71") (pinfunction "PA7_(AD7)_71") (pintype "bidirectional"))
    )
    (net (code "16") (name "/D30") (class "Default")
      (node (ref "ATMEGA") (pin "60") (pinfunction "PC7_(A15)_60") (pintype "bidirectional"))
    )
    (net (code "17") (name "/D31") (class "Default")
      (node (ref "ATMEGA") (pin "59") (pinfunction "PC6_(A14)_59") (pintype "bidirectional"))
    )
    (net (code "18") (name "/D39") (class "Default")
      (node (ref "ATMEGA") (pin "70") (pinfunction "PG2_(ALE)_70") (pintype "bidirectional"))
    )
    (net (code "19") (name "/D40") (class "Default")
      (node (ref "ATMEGA") (pin "52") (pinfunction "PG1_(~{RD})_52") (pintype "bidirectional"))
    )
    (net (code "20") (name "/D41") (class "Default")
      (node (ref "ATMEGA") (pin "51") (pinfunction "PG0_(~{WR})_51") (pintype "bidirectional"))
    )
    (net (code "21") (name "/D44") (class "Default")
      (node (ref "ATMEGA") (pin "40") (pinfunction "OC5C)_PL5_40") (pintype "bidirectional"))
    )
    (net (code "22") (name "/D45") (class "Default")
      (node (ref "ATMEGA") (pin "39") (pinfunction "(OC5B)_PL4_39") (pintype "bidirectional"))
      (node (ref "JP3") (pin "6") (pinfunction "6_6") (pintype "passive"))
    )
    (net (code "23") (name "/D46") (class "Default")
      (node (ref "ATMEGA") (pin "38") (pinfunction "(OC5A)_PL3_38") (pintype "bidirectional"))
      (node (ref "JP3") (pin "5") (pinfunction "5_5") (pintype "passive"))
    )
    (net (code "24") (name "/D47") (class "Default")
      (node (ref "ATMEGA") (pin "37") (pinfunction "(T5)_PL2_37") (pintype "bidirectional"))
    )
    (net (code "25") (name "/D50") (class "Default")
      (node (ref "ATMEGA") (pin "22") (pinfunction "(MISO/PCINT3)_PB3_22") (pintype "bidirectional"))
      (node (ref "CAN-CONTROLLER") (pin "15") (pinfunction "SO_15") (pintype "output"))
      (node (ref "JP2") (pin "1") (pinfunction "1_1") (pintype "passive"))
    )
    (net (code "26") (name "/D51") (class "Default")
      (node (ref "ATMEGA") (pin "21") (pinfunction "(MOSI/PCINT2)_PB2_21") (pintype "bidirectional"))
      (node (ref "CAN-CONTROLLER") (pin "14") (pinfunction "SI_14") (pintype "input"))
      (node (ref "JP1") (pin "2") (pinfunction "2_2") (pintype "passive"))
    )
    (net (code "27") (name "/D52") (class "Default")
      (node (ref "ATMEGA") (pin "20") (pinfunction "(SCK/PCINT1)_PB1_20") (pintype "bidirectional"))
      (node (ref "CAN-CONTROLLER") (pin "13") (pinfunction "SCK_13") (pintype "input"))
      (node (ref "JP2") (pin "2") (pinfunction "2_2") (pintype "passive"))
    )
    (net (code "28") (name "/D53") (class "Default")
      (node (ref "ATMEGA") (pin "19") (pinfunction "(~{SS/PCINT0})_PB0_19") (pintype "bidirectional"))
    )
    (net (code "29") (name "/DTR") (class "Default")
      (node (ref "C42") (pin "1") (pinfunction "1_1") (pintype "passive"))
      (node (ref "JP4") (pin "DTR") (pinfunction "1_DTR") (pintype "passive"))
      (node (ref "U$1") (pin "2") (pinfunction "P$2_2") (pintype "bidirectional"))
    )
    (net (code "30") (name "/FF1A") (class "Default")
      (node (ref "ATMEGA") (pin "77") (pinfunction "PA1_(AD1)_77") (pintype "bidirectional"))
      (node (ref "U$25") (pin "25") (pinfunction "FF1_25") (pintype "output"))
    )
    (net (code "31") (name "/FF1B") (class "Default")
      (node (ref "ATMEGA") (pin "42") (pinfunction "PL7_42") (pintype "bidirectional"))
      (node (ref "U$26") (pin "25") (pinfunction "FF1_25") (pintype "output"))
    )
    (net (code "32") (name "/FF1C") (class "Default")
      (node (ref "ATMEGA") (pin "56") (pinfunction "PC3_(A11)_56") (pintype "bidirectional"))
      (node (ref "U$27") (pin "25") (pinfunction "FF1_25") (pintype "output"))
    )
    (net (code "33") (name "/FF1D") (class "Default")
      (node (ref "ATMEGA") (pin "64") (pinfunction "PJ1_(TXD3/PCINT10)_64") (pintype "bidirectional"))
      (node (ref "U$28") (pin "25") (pinfunction "FF1_25") (pintype "output"))
    )
    (net (code "34") (name "/FF1E") (class "Default")
      (node (ref "ATMEGA") (pin "94") (pinfunction "PF3_(ADC3)_94") (pintype "bidirectional"))
      (node (ref "U$29") (pin "25") (pinfunction "FF1_25") (pintype "output"))
    )
    (net (code "35") (name "/FF1F") (class "Default")
      (node (ref "ATMEGA") (pin "86") (pinfunction "PK3_(ADC11/PCINT19)_86") (pintype "bidirectional"))
      (node (ref "U$30") (pin "25") (pinfunction "FF1_25") (pintype "output"))
    )
    (net (code "36") (name "/FF2A") (class "Default")
      (node (ref "ATMEGA") (pin "78") (pinfunction "PA0_(AD0)_78") (pintype "bidirectional"))
      (node (ref "U$25") (pin "26") (pinfunction "FF2_26") (pintype "output"))
    )
    (net (code "37") (name "/FF2B") (class "Default")
      (node (ref "ATMEGA") (pin "41") (pinfunction "PL6_41") (pintype "bidirectional"))
      (node (ref "U$26") (pin "26") (pinfunction "FF2_26") (pintype "output"))
    )
    (net (code "38") (name "/FF2C") (class "Default")
      (node (ref "ATMEGA") (pin "57") (pinfunction "PC4_(A12)_57") (pintype "bidirectional"))
      (node (ref "U$27") (pin "26") (pinfunction "FF2_26") (pintype "output"))
    )
    (net (code "39") (name "/FF2D") (class "Default")
      (node (ref "ATMEGA") (pin "63") (pinfunction "PJ0_(RXD3/PCINT9)_63") (pintype "bidirectional"))
      (node (ref "U$28") (pin "26") (pinfunction "FF2_26") (pintype "output"))
    )
    (net (code "40") (name "/FF2E") (class "Default")
      (node (ref "ATMEGA") (pin "93") (pinfunction "PF4_(ADC4/TCK)_93") (pintype "bidirectional"))
      (node (ref "U$29") (pin "26") (pinfunction "FF2_26") (pintype "output"))
    )
    (net (code "41") (name "/FF2F") (class "Default")
      (node (ref "ATMEGA") (pin "85") (pinfunction "PK4_(ADC12/PCINT20)_85") (pintype "bidirectional"))
      (node (ref "U$30") (pin "26") (pinfunction "FF2_26") (pintype "output"))
    )
    (net (code "42") (name "/GHA1") (class "Default")
      (node (ref "U$2") (pin "19") (pinfunction "P$19_19") (pintype "bidirectional"))
      (node (ref "U$25") (pin "10") (pinfunction "GHA_10") (pintype "output"))
    )
    (net (code "43") (name "/GHA2") (class "Default")
      (node (ref "U$2") (pin "12") (pinfunction "P$12_12") (pintype "bidirectional"))
      (node (ref "U$26") (pin "10") (pinfunction "GHA_10") (pintype "output"))
    )
    (net (code "44") (name "/GHA3") (class "Default")
      (node (ref "U$2") (pin "23") (pinfunction "P$23_23") (pintype "bidirectional"))
      (node (ref "U$27") (pin "10") (pinfunction "GHA_10") (pintype "output"))
    )
    (net (code "45") (name "/GHA4") (class "Default")
      (node (ref "U$2") (pin "13") (pinfunction "P$13_13") (pintype "bidirectional"))
      (node (ref "U$28") (pin "10") (pinfunction "GHA_10") (pintype "output"))
    )
    (net (code "46") (name "/GHA5") (class "Default")
      (node (ref "U$2") (pin "6") (pinfunction "P$6_6") (pintype "bidirectional"))
      (node (ref "U$29") (pin "10") (pinfunction "GHA_10") (pintype "output"))
    )
    (net (code "47") (name "/GHA6") (class "Default")
      (node (ref "U$2") (pin "4") (pinfunction "P$4_4") (pintype "bidirectional"))
      (node (ref "U$30") (pin "10") (pinfunction "GHA_10") (pintype "output"))
    )
    (net (code "48") (name "/GHB1") (class "Default")
      (node (ref "U$2") (pin "10") (pinfunction "P$10_10") (pintype "bidirectional"))
      (node (ref "U$25") (pin "5") (pinfunction "GHB_5") (pintype "output"))
    )
    (net (code "49") (name "/GHB2") (class "Default")
      (node (ref "U$2") (pin "21") (pinfunction "P$21_21") (pintype "bidirectional"))
      (node (ref "U$26") (pin "5") (pinfunction "GHB_5") (pintype "output"))
    )
    (net (code "50") (name "/GHB3") (class "Default")
      (node (ref "U$2") (pin "20") (pinfunction "P$20_20") (pintype "bidirectional"))
      (node (ref "U$27") (pin "5") (pinfunction "GHB_5") (pintype "output"))
    )
    (net (code "51") (name "/GHB4") (class "Default")
      (node (ref "U$2") (pin "2") (pinfunction "P$2_2") (pintype "bidirectional"))
      (node (ref "U$28") (pin "5") (pinfunction "GHB_5") (pintype "output"))
    )
    (net (code "52") (name "/GHB5") (class "Default")
      (node (ref "U$2") (pin "17") (pinfunction "P$17_17") (pintype "bidirectional"))
      (node (ref "U$29") (pin "5") (pinfunction "GHB_5") (pintype "output"))
    )
    (net (code "53") (name "/GHB6") (class "Default")
      (node (ref "U$2") (pin "15") (pinfunction "P$15_15") (pintype "bidirectional"))
      (node (ref "U$30") (pin "5") (pinfunction "GHB_5") (pintype "output"))
    )
    (net (code "54") (name "/GLA1") (class "Default")
      (node (ref "U$2") (pin "7") (pinfunction "P$7_7") (pintype "bidirectional"))
      (node (ref "U$25") (pin "12") (pinfunction "GLA_12") (pintype "output"))
    )
    (net (code "55") (name "/GLA2") (class "Default")
      (node (ref "U$2") (pin "24") (pinfunction "P$24_24") (pintype "bidirectional"))
      (node (ref "U$26") (pin "12") (pinfunction "GLA_12") (pintype "output"))
    )
    (net (code "56") (name "/GLA3") (class "Default")
      (node (ref "U$2") (pin "11") (pinfunction "P$11_11") (pintype "bidirectional"))
      (node (ref "U$27") (pin "12") (pinfunction "GLA_12") (pintype "output"))
    )
    (net (code "57") (name "/GLA4") (class "Default")
      (node (ref "U$2") (pin "14") (pinfunction "P$14_14") (pintype "bidirectional"))
      (node (ref "U$28") (pin "12") (pinfunction "GLA_12") (pintype "output"))
    )
    (net (code "58") (name "/GLA5") (class "Default")
      (node (ref "U$2") (pin "5") (pinfunction "P$5_5") (pintype "bidirectional"))
      (node (ref "U$29") (pin "12") (pinfunction "GLA_12") (pintype "output"))
    )
    (net (code "59") (name "/GLA6") (class "Default")
      (node (ref "U$2") (pin "3") (pinfunction "P$3_3") (pintype "bidirectional"))
      (node (ref "U$30") (pin "12") (pinfunction "GLA_12") (pintype "output"))
    )
    (net (code "60") (name "/GLB1") (class "Default")
      (node (ref "U$2") (pin "22") (pinfunction "P$22_22") (pintype "bidirectional"))
      (node (ref "U$25") (pin "3") (pinfunction "GLB_3") (pintype "output"))
    )
    (net (code "61") (name "/GLB2") (class "Default")
      (node (ref "U$2") (pin "9") (pinfunction "P$9_9") (pintype "bidirectional"))
      (node (ref "U$26") (pin "3") (pinfunction "GLB_3") (pintype "output"))
    )
    (net (code "62") (name "/GLB3") (class "Default")
      (node (ref "U$2") (pin "8") (pinfunction "P$8_8") (pintype "bidirectional"))
      (node (ref "U$27") (pin "3") (pinfunction "GLB_3") (pintype "output"))
    )
    (net (code "63") (name "/GLB4") (class "Default")
      (node (ref "U$2") (pin "1") (pinfunction "P$1_1") (pintype "bidirectional"))
      (node (ref "U$28") (pin "3") (pinfunction "GLB_3") (pintype "output"))
    )
    (net (code "64") (name "/GLB5") (class "Default")
      (node (ref "U$2") (pin "18") (pinfunction "P$18_18") (pintype "bidirectional"))
      (node (ref "U$29") (pin "3") (pinfunction "GLB_3") (pintype "output"))
    )
    (net (code "65") (name "/GLB6") (class "Default")
      (node (ref "U$2") (pin "16") (pinfunction "P$16_16") (pintype "bidirectional"))
      (node (ref "U$30") (pin "3") (pinfunction "GLB_3") (pintype "output"))
    )
    (net (code "66") (name "/GNDBUS") (class "Default")
      (node (ref "C55") (pin "1") (pinfunction "1_1") (pintype "passive"))
      (node (ref "C56") (pin "P$2") (pinfunction "-_P$2") (pintype "passive"))
      (node (ref "CAN-TRANSCEIVER") (pin "5") (pinfunction "GND2_5") (pintype "passive"))
      (node (ref "DC-DC") (pin "13") (pinfunction "0VOUT_13") (pintype "output"))
    )
    (net (code "67") (name "/INT") (class "Default")
      (node (ref "ATMEGA") (pin "6") (pinfunction "(OC3B/INT4)_PE4_6") (pintype "bidirectional"))
      (node (ref "CAN-CONTROLLER") (pin "12") (pinfunction "~{INT}_12") (pintype "output"))
      (node (ref "INT") (pin "C") (pinfunction "C_C") (pintype "passive"))
    )
    (net (code "68") (name "/N$32") (class "Default")
      (node (ref "ATMEGA") (pin "79") (pinfunction "PJ7_79") (pintype "bidirectional"))
    )
    (net (code "69") (name "/N$36A") (class "Default")
      (node (ref "CAN-CONTROLLER") (pin "17") (pinfunction "~{RESET}_17") (pintype "input"))
      (node (ref "R78") (pin "2") (pinfunction "2_2") (pintype "passive"))
    )
    (net (code "70") (name "/N$41A") (class "Default")
      (node (ref "CAN-CONTROLLER") (pin "10") (pinfunction "~{RX1BF}_10") (pintype "output"))
    )
    (net (code "71") (name "/N$42A") (class "Default")
      (node (ref "CAN-CONTROLLER") (pin "11") (pinfunction "~{RX0BF}_11") (pintype "output"))
    )
    (net (code "72") (name "/N$46A") (class "Default")
      (node (ref "CAN-CONTROLLER") (pin "3") (pinfunction "CLKOUT/SOF_3") (pintype "output"))
    )
    (net (code "73") (name "/N$73") (class "Default")
      (node (ref "ATMEGA") (pin "4") (pinfunction "(XCK0/AIN0)_PE2_4") (pintype "bidirectional"))
    )
    (net (code "74") (name "/N$77") (class "Default")
      (node (ref "ATMEGA") (pin "8") (pinfunction "(T3/INT6)_PE6_8") (pintype "bidirectional"))
    )
    (net (code "75") (name "/N$78") (class "Default")
      (node (ref "ATMEGA") (pin "9") (pinfunction "(CLKO/ICP3/INT7)_PE7_9") (pintype "bidirectional"))
    )
    (net (code "76") (name "/N$90") (class "Default")
      (node (ref "ATMEGA") (pin "28") (pinfunction "(TOSC2)_PG3_28") (pintype "bidirectional"))
    )
    (net (code "77") (name "/N$91") (class "Default")
      (node (ref "ATMEGA") (pin "29") (pinfunction "(TOSC1)_PG4_29") (pintype "bidirectional"))
    )
    (net (code "78") (name "/N$95") (class "Default")
      (node (ref "ATMEGA") (pin "14") (pinfunction "(XCK2)_PH2_14") (pintype "bidirectional"))
    )
    (net (code "79") (name "/N$100") (class "Default")
      (node (ref "ATMEGA") (pin "27") (pinfunction "(T4)_PH7_27") (pintype "bidirectional"))
    )
    (net (code "80") (name "/N$106") (class "Default")
      (node (ref "ATMEGA") (pin "68") (pinfunction "PJ5_(PCINT14)_68") (pintype "bidirectional"))
    )
    (net (code "81") (name "/N$125") (class "Default")
      (node (ref "ATMEGA") (pin "84") (pinfunction "PK5_(ADC13/PCINT21)_84") (pintype "bidirectional"))
    )
    (net (code "82") (name "/N$126") (class "Default")
      (node (ref "ATMEGA") (pin "83") (pinfunction "PK6_(ADC14/PCINT22)_83") (pintype "bidirectional"))
    )
    (net (code "83") (name "/N$127") (class "Default")
      (node (ref "ATMEGA") (pin "82") (pinfunction "PK7_(ADC15/PCINT23)_82") (pintype "bidirectional"))
    )
    (net (code "84") (name "/NC") (class "Default")
      (node (ref "U$1") (pin "18") (pinfunction "P$18_18") (pintype "bidirectional"))
    )
    (net (code "85") (name "/OSC1") (class "Default")
      (node (ref "16MHZ") (pin "2") (pinfunction "2_2") (pintype "passive"))
      (node (ref "C54") (pin "1") (pinfunction "1_1") (pintype "passive"))
      (node (ref "CAN-CONTROLLER") (pin "8") (pinfunction "OSC1_8") (pintype "input"))
    )
    (net (code "86") (name "/OSC2") (class "Default")
      (node (ref "16MHZ") (pin "1") (pinfunction "1_1") (pintype "passive"))
      (node (ref "C53") (pin "1") (pinfunction "1_1") (pintype "passive"))
      (node (ref "CAN-CONTROLLER") (pin "7") (pinfunction "OSC2_7") (pintype "output"))
    )
    (net (code "87") (name "/PHASE1") (class "Default")
      (node (ref "ATMEGA") (pin "26") (pinfunction "(OC0A/OC1C/PCINT7)_PB7_26") (pintype "bidirectional"))
      (node (ref "U$25") (pin "19") (pinfunction "PHASE_19") (pintype "input"))
    )
    (net (code "88") (name "/PHASE2") (class "Default")
      (node (ref "ATMEGA") (pin "1") (pinfunction "(OC0B)_PG5_1") (pintype "bidirectional"))
      (node (ref "U$26") (pin "19") (pinfunction "PHASE_19") (pintype "input"))
    )
    (net (code "89") (name "/PHASE3") (class "Default")
      (node (ref "ATMEGA") (pin "24") (pinfunction "(OC1A/PCINT5)_PB5_24") (pintype "bidirectional"))
      (node (ref "U$27") (pin "19") (pinfunction "PHASE_19") (pintype "input"))
    )
    (net (code "90") (name "/PHASE4") (class "Default")
      (node (ref "ATMEGA") (pin "25") (pinfunction "(OC1B/PCINT6)_PB6_25") (pintype "bidirectional"))
      (node (ref "U$28") (pin "19") (pinfunction "PHASE_19") (pintype "input"))
    )
    (net (code "91") (name "/PHASE5") (class "Default")
      (node (ref "ATMEGA") (pin "23") (pinfunction "(OC2A/PCINT4)_PB4_23") (pintype "bidirectional"))
      (node (ref "U$29") (pin "19") (pinfunction "PHASE_19") (pintype "input"))
    )
    (net (code "92") (name "/PHASE6") (class "Default")
      (node (ref "ATMEGA") (pin "18") (pinfunction "(OC2B)_PH6_18") (pintype "bidirectional"))
      (node (ref "U$30") (pin "19") (pinfunction "PHASE_19") (pintype "input"))
    )
    (net (code "93") (name "/PWM1") (class "Default")
      (node (ref "ATMEGA") (pin "75") (pinfunction "PA3_(AD3)_75") (pintype "bidirectional"))
      (node (ref "U$25") (pin "22") (pinfunction "PWML_22") (pintype "input"))
      (node (ref "U$25") (pin "23") (pinfunction "PWMH_23") (pintype "input"))
    )
    (net (code "94") (name "/PWM2") (class "Default")
      (node (ref "ATMEGA") (pin "46") (pinfunction "(TXD1/INT3)_PD3_46") (pintype "bidirectional"))
      (node (ref "U$26") (pin "22") (pinfunction "PWML_22") (pintype "input"))
      (node (ref "U$26") (pin "23") (pinfunction "PWMH_23") (pintype "input"))
    )
    (net (code "95") (name "/PWM3") (class "Default")
      (node (ref "ATMEGA") (pin "54") (pinfunction "PC1_(A9)_54") (pintype "bidirectional"))
      (node (ref "U$27") (pin "22") (pinfunction "PWML_22") (pintype "input"))
      (node (ref "U$27") (pin "23") (pinfunction "PWMH_23") (pintype "input"))
    )
    (net (code "96") (name "/PWM4") (class "Default")
      (node (ref "ATMEGA") (pin "66") (pinfunction "PJ3_(PCINT12)_66") (pintype "bidirectional"))
      (node (ref "U$28") (pin "22") (pinfunction "PWML_22") (pintype "input"))
      (node (ref "U$28") (pin "23") (pinfunction "PWMH_23") (pintype "input"))
    )
    (net (code "97") (name "/PWM5") (class "Default")
      (node (ref "ATMEGA") (pin "96") (pinfunction "PF1_(ADC1)_96") (pintype "bidirectional"))
      (node (ref "U$29") (pin "22") (pinfunction "PWML_22") (pintype "input"))
      (node (ref "U$29") (pin "23") (pinfunction "PWMH_23") (pintype "input"))
    )
    (net (code "98") (name "/PWM6") (class "Default")
      (node (ref "ATMEGA") (pin "88") (pinfunction "PK1_(ADC9/PCINT17)_88") (pintype "bidirectional"))
      (node (ref "U$30") (pin "22") (pinfunction "PWML_22") (pintype "input"))
      (node (ref "U$30") (pin "23") (pinfunction "PWMH_23") (pintype "input"))
    )
    (net (code "99") (name "/RES") (class "Default")
      (node (ref "ATMEGA") (pin "30") (pinfunction "~{RESET}_30") (pintype "input"))
      (node (ref "C42") (pin "2") (pinfunction "2_2") (pintype "passive"))
      (node (ref "C44") (pin "1") (pinfunction "1_1") (pintype "passive"))
      (node (ref "JP2") (pin "3") (pinfunction "3_3") (pintype "passive"))
      (node (ref "R53") (pin "2") (pinfunction "2_2") (pintype "passive"))
      (node (ref "R62") (pin "2") (pinfunction "2_2") (pintype "passive"))
      (node (ref "SWITCHING-CHIP-DIODE") (pin "A") (pinfunction "A_A") (pintype "passive"))
      (node (ref "U$35") (pin "3") (pinfunction "3_3") (pintype "bidirectional"))
      (node (ref "U$35") (pin "4") (pinfunction "4_4") (pintype "bidirectional"))
    )
    (net (code "100") (name "/RESET1") (class "Default")
      (node (ref "ATMEGA") (pin "76") (pinfunction "PA2_(AD2)_76") (pintype "bidirectional"))
      (node (ref "U$25") (pin "24") (pinfunction "RESET_24") (pintype "input"))
    )
    (net (code "101") (name "/RESET2") (class "Default")
      (node (ref "ATMEGA") (pin "45") (pinfunction "(RXD1/INT2)_PD2_45") (pintype "bidirectional"))
      (node (ref "U$26") (pin "24") (pinfunction "RESET_24") (pintype "input"))
    )
    (net (code "102") (name "/RESET3") (class "Default")
      (node (ref "ATMEGA") (pin "55") (pinfunction "PC2_(A10)_55") (pintype "bidirectional"))
      (node (ref "U$27") (pin "24") (pinfunction "RESET_24") (pintype "input"))
    )
    (net (code "103") (name "/RESET4") (class "Default")
      (node (ref "ATMEGA") (pin "65") (pinfunction "PJ2_(XCK3/PCINT11)_65") (pintype "bidirectional"))
      (node (ref "U$28") (pin "24") (pinfunction "RESET_24") (pintype "input"))
    )
    (net (code "104") (name "/RESET5") (class "Default")
      (node (ref "ATMEGA") (pin "95") (pinfunction "PF2_(ADC2)_95") (pintype "bidirectional"))
      (node (ref "U$29") (pin "24") (pinfunction "RESET_24") (pintype "input"))
    )
    (net (code "105") (name "/RESET6") (class "Default")
      (node (ref "ATMEGA") (pin "87") (pinfunction "PK2_(ADC10/PCINT18)_87") (pintype "bidirectional"))
      (node (ref "U$30") (pin "24") (pinfunction "RESET_24") (pintype "input"))
    )
    (net (code "106") (name "/RX-CAN") (class "Default")
      (node (ref "CAN-CONTROLLER") (pin "2") (pinfunction "RXCAN_2") (pintype "input"))
      (node (ref "CAN-TRANSCEIVER") (pin "2") (pinfunction "RXD_2") (pintype "output"))
      (node (ref "RX-CAN") (pin "C") (pinfunction "C_C") (pintype "passive"))
    )
    (net (code "107") (name "/RX0") (class "Default")
      (node (ref "ATMEGA") (pin "2") (pinfunction "(RXD0/PCINT8)_PE0_2") (pintype "bidirectional"))
      (node (ref "JP4") (pin "TXO") (pinfunction "3_TXO") (pintype "passive"))
      (node (ref "R69") (pin "2") (pinfunction "2_2") (pintype "passive"))
      (node (ref "U$1") (pin "13") (pinfunction "P$13_13") (pintype "bidirectional"))
    )
    (net (code "108") (name "/RX2") (class "Default")
      (node (ref "ATMEGA") (pin "12") (pinfunction "(RXD2)_PH0_12") (pintype "bidirectional"))
    )
    (net (code "109") (name "/SA1") (class "Default")
      (node (ref "C2") (pin "1") (pinfunction "C1_1") (pintype "passive"))
      (node (ref "U$1") (pin "20") (pinfunction "P$20_20") (pintype "bidirectional"))
      (node (ref "U$25") (pin "11") (pinfunction "SA_11") (pintype "input"))
    )
    (net (code "110") (name "/SA2") (class "Default")
      (node (ref "C7") (pin "1") (pinfunction "C1_1") (pintype "passive"))
      (node (ref "U$1") (pin "7") (pinfunction "P$7_7") (pintype "bidirectional"))
      (node (ref "U$26") (pin "11") (pinfunction "SA_11") (pintype "input"))
    )
    (net (code "111") (name "/SA3") (class "Default")
      (node (ref "C12") (pin "1") (pinfunction "C1_1") (pintype "passive"))
      (node (ref "U$1") (pin "8") (pinfunction "P$8_8") (pintype "bidirectional"))
      (node (ref "U$27") (pin "11") (pinfunction "SA_11") (pintype "input"))
    )
    (net (code "112") (name "/SA4") (class "Default")
      (node (ref "C17") (pin "1") (pinfunction "C1_1") (pintype "passive"))
      (node (ref "U$1") (pin "11") (pinfunction "P$11_11") (pintype "bidirectional"))
      (node (ref "U$28") (pin "11") (pinfunction "SA_11") (pintype "input"))
    )
    (net (code "113") (name "/SA5") (class "Default")
      (node (ref "C22") (pin "1") (pinfunction "C1_1") (pintype "passive"))
      (node (ref "U$1") (pin "12") (pinfunction "P$12_12") (pintype "bidirectional"))
      (node (ref "U$29") (pin "11") (pinfunction "SA_11") (pintype "input"))
    )
    (net (code "114") (name "/SA6") (class "Default")
      (node (ref "C27") (pin "1") (pinfunction "C1_1") (pintype "passive"))
      (node (ref "U$1") (pin "24") (pinfunction "P$24_24") (pintype "bidirectional"))
      (node (ref "U$30") (pin "11") (pinfunction "SA_11") (pintype "input"))
    )
    (net (code "115") (name "/SB1") (class "Default")
      (node (ref "C3") (pin "1") (pinfunction "C1_1") (pintype "passive"))
      (node (ref "U$1") (pin "19") (pinfunction "P$19_19") (pintype "bidirectional"))
      (node (ref "U$25") (pin "4") (pinfunction "SB_4") (pintype "input"))
    )
    (net (code "116") (name "/SB2") (class "Default")
      (node (ref "C8") (pin "1") (pinfunction "C1_1") (pintype "passive"))
      (node (ref "U$1") (pin "21") (pinfunction "P$21_21") (pintype "bidirectional"))
      (node (ref "U$26") (pin "4") (pinfunction "SB_4") (pintype "input"))
    )
    (net (code "117") (name "/SB3") (class "Default")
      (node (ref "C13") (pin "1") (pinfunction "C1_1") (pintype "passive"))
      (node (ref "U$1") (pin "9") (pinfunction "P$9_9") (pintype "bidirectional"))
      (node (ref "U$27") (pin "4") (pinfunction "SB_4") (pintype "input"))
    )
    (net (code "118") (name "/SB4") (class "Default")
      (node (ref "C18") (pin "1") (pinfunction "C1_1") (pintype "passive"))
      (node (ref "U$1") (pin "23") (pinfunction "P$23_23") (pintype "bidirectional"))
      (node (ref "U$28") (pin "4") (pinfunction "SB_4") (pintype "input"))
    )
    (net (code "119") (name "/SB5") (class "Default")
      (node (ref "C23") (pin "1") (pinfunction "C1_1") (pintype "passive"))
      (node (ref "U$1") (pin "10") (pinfunction "P$10_10") (pintype "bidirectional"))
      (node (ref "U$29") (pin "4") (pinfunction "SB_4") (pintype "input"))
    )
    (net (code "120") (name "/SB6") (class "Default")
      (node (ref "C28") (pin "1") (pinfunction "C1_1") (pintype "passive"))
      (node (ref "U$1") (pin "22") (pinfunction "P$22_22") (pintype "bidirectional"))
      (node (ref "U$30") (pin "4") (pinfunction "SB_4") (pintype "input"))
    )
    (net (code "121") (name "/SCL") (class "Default")
      (node (ref "ATMEGA") (pin "43") (pinfunction "(SCL/INT0)_PD0_43") (pintype "bidirectional"))
      (node (ref "JP5") (pin "2") (pinfunction "2_2") (pintype "passive"))
      (node (ref "R2") (pin "2") (pinfunction "2_2") (pintype "passive"))
      (node (ref "U$1") (pin "16") (pinfunction "P$16_16") (pintype "bidirectional"))
      (node (ref "U$4") (pin "4") (pinfunction "SCL_4") (pintype "bidirectional"))
    )
    (net (code "122") (name "/SDA") (class "Default")
      (node (ref "ATMEGA") (pin "44") (pinfunction "(SDA/INT1)_PD1_44") (pintype "bidirectional"))
      (node (ref "JP5") (pin "3") (pinfunction "3_3") (pintype "passive"))
      (node (ref "R3") (pin "2") (pinfunction "2_2") (pintype "passive"))
      (node (ref "U$1") (pin "4") (pinfunction "P$4_4") (pintype "bidirectional"))
      (node (ref "U$4") (pin "6") (pinfunction "SDA_6") (pintype "bidirectional"))
    )
    (net (code "123") (name "/SR1") (class "Default")
      (node (ref "ATMEGA") (pin "74") (pinfunction "PA4_(AD4)_74") (pintype "bidirectional"))
      (node (ref "U$25") (pin "21") (pinfunction "SR_21") (pintype "input"))
    )
    (net (code "124") (name "/SR2") (class "Default")
      (node (ref "ATMEGA") (pin "47") (pinfunction "(ICP1)_PD4_47") (pintype "bidirectional"))
      (node (ref "U$26") (pin "21") (pinfunction "SR_21") (pintype "input"))
    )
    (net (code "125") (name "/SR3") (class "Default")
      (node (ref "ATMEGA") (pin "53") (pinfunction "PC0_(A8)_53") (pintype "bidirectional"))
      (node (ref "U$27") (pin "21") (pinfunction "SR_21") (pintype "input"))
    )
    (net (code "126") (name "/SR4") (class "Default")
      (node (ref "ATMEGA") (pin "67") (pinfunction "PJ4_(PCINT13)_67") (pintype "bidirectional"))
      (node (ref "U$28") (pin "21") (pinfunction "SR_21") (pintype "input"))
    )
    (net (code "127") (name "/SR5") (class "Default")
      (node (ref "ATMEGA") (pin "97") (pinfunction "PF0_(ADC0)_97") (pintype "bidirectional"))
      (node (ref "U$29") (pin "21") (pinfunction "SR_21") (pintype "input"))
    )
    (net (code "128") (name "/SR6") (class "Default")
      (node (ref "ATMEGA") (pin "89") (pinfunction "PK0_(ADC8/PCINT16)_89") (pintype "bidirectional"))
      (node (ref "U$30") (pin "21") (pinfunction "SR_21") (pintype "input"))
    )
    (net (code "129") (name "/TX-CAN") (class "Default")
      (node (ref "CAN-CONTROLLER") (pin "1") (pinfunction "TXCAN_1") (pintype "output"))
      (node (ref "CAN-TRANSCEIVER") (pin "3") (pinfunction "TXD_3") (pintype "input"))
      (node (ref "TX-CAN") (pin "C") (pinfunction "C_C") (pintype "passive"))
    )
    (net (code "130") (name "/TX0") (class "Default")
      (node (ref "ATMEGA") (pin "3") (pinfunction "(TXD0)_PE1_3") (pintype "bidirectional"))
      (node (ref "JP4") (pin "RXI") (pinfunction "2_RXI") (pintype "passive"))
      (node (ref "R70") (pin "2") (pinfunction "2_2") (pintype "passive"))
      (node (ref "U$1") (pin "1") (pinfunction "P$1_1") (pintype "bidirectional"))
    )
    (net (code "131") (name "/TX2") (class "Default")
      (node (ref "ATMEGA") (pin "13") (pinfunction "(TXD2)_PH1_13") (pintype "bidirectional"))
    )
    (net (code "132") (name "/VBUS") (class "Default")
      (node (ref "C55") (pin "2") (pinfunction "2_2") (pintype "passive"))
      (node (ref "CAN-TRANSCEIVER") (pin "8") (pinfunction "VCC2_8") (pintype "power_in"))
      (node (ref "DC-DC") (pin "14") (pinfunction "VO_14") (pintype "output"))
      (node (ref "R79") (pin "1") (pinfunction "1_1") (pintype "passive"))
    )
    (net (code "133") (name "/VREC") (class "Default")
      (node (ref "C56") (pin "P$1") (pinfunction "+_P$1") (pintype "passive"))
      (node (ref "DC-DC") (pin "12") (pinfunction "VREC_12") (pintype "input"))
      (node (ref "DC-DC") (pin "16") (pinfunction "EN_16") (pintype "input"))
    )
    (net (code "134") (name "/XTAL1") (class "Default")
      (node (ref "ATMEGA") (pin "34") (pinfunction "XTAL1_34") (pintype "input"))
      (node (ref "C40") (pin "1") (pinfunction "1_1") (pintype "passive"))
      (node (ref "Q2") (pin "1") (pinfunction "1_1") (pintype "passive"))
      (node (ref "R58") (pin "1") (pinfunction "1_1") (pintype "passive"))
    )
    (net (code "135") (name "/XTAL2") (class "Default")
      (node (ref "ATMEGA") (pin "33") (pinfunction "XTAL2_33") (pintype "output"))
      (node (ref "C41") (pin "1") (pinfunction "1_1") (pintype "passive"))
      (node (ref "Q2") (pin "2") (pinfunction "2_2") (pintype "passive"))
      (node (ref "R58") (pin "2") (pinfunction "2_2") (pintype "passive"))
    )
    (net (code "136") (name "GND") (class "Default")
      (node (ref "ATMEGA") (pin "11") (pinfunction "GND_2_11") (pintype "passive"))
      (node (ref "ATMEGA") (pin "32") (pinfunction "GND_4_32") (pintype "passive"))
      (node (ref "ATMEGA") (pin "62") (pinfunction "GND_3_62") (pintype "passive"))
      (node (ref "ATMEGA") (pin "81") (pinfunction "GND_5_81") (pintype "passive"))
      (node (ref "ATMEGA") (pin "99") (pinfunction "GND_99") (pintype "passive"))
      (node (ref "C10") (pin "1") (pinfunction "C1_1") (pintype "passive"))
      (node (ref "C14") (pin "2") (pinfunction "C2_2") (pintype "passive"))
      (node (ref "C15") (pin "1") (pinfunction "C1_1") (pintype "passive"))
      (node (ref "C19") (pin "2") (pinfunction "C2_2") (pintype "passive"))
      (node (ref "C20") (pin "1") (pinfunction "C1_1") (pintype "passive"))
      (node (ref "C24") (pin "2") (pinfunction "C2_2") (pintype "passive"))
      (node (ref "C25") (pin "1") (pinfunction "C1_1") (pintype "passive"))
      (node (ref "C29") (pin "2") (pinfunction "C2_2") (pintype "passive"))
      (node (ref "C30") (pin "1") (pinfunction "C1_1") (pintype "passive"))
      (node (ref "C33") (pin "2") (pinfunction "2_2") (pintype "passive"))
      (node (ref "C34") (pin "2") (pinfunction "2_2") (pintype "passive"))
      (node (ref "C35") (pin "2") (pinfunction "2_2") (pintype "passive"))
      (node (ref "C36") (pin "2") (pinfunction "2_2") (pintype "passive"))
      (node (ref "C37") (pin "2") (pinfunction "2_2") (pintype "passive"))
      (node (ref "C4") (pin "2") (pinfunction "C2_2") (pintype "passive"))
      (node (ref "C40") (pin "2") (pinfunction "2_2") (pintype "passive"))
      (node (ref "C41") (pin "2") (pinfunction "2_2") (pintype "passive"))
      (node (ref "C44") (pin "2") (pinfunction "2_2") (pintype "passive"))
      (node (ref "C5") (pin "1") (pinfunction "C1_1") (pintype "passive"))
      (node (ref "C53") (pin "2") (pinfunction "2_2") (pintype "passive"))
      (node (ref "C54") (pin "2") (pinfunction "2_2") (pintype "passive"))
      (node (ref "C57") (pin "1") (pinfunction "1_1") (pintype "passive"))
      (node (ref "C9") (pin "2") (pinfunction "C2_2") (pintype "passive"))
      (node (ref "CAN-CONTROLLER") (pin "9") (pinfunction "VSS_9") (pintype "power_in"))
      (node (ref "CAN-TRANSCEIVER") (pin "4") (pinfunction "GND1_4") (pintype "passive"))
      (node (ref "DC-DC") (pin "26") (pinfunction "0VIN_2_26") (pintype "passive"))
      (node (ref "DC-DC") (pin "27") (pinfunction "0VIN_27") (pintype "passive"))
      (node (ref "JP1") (pin "1") (pinfunction "1_1") (pintype "passive"))
      (node (ref "JP3") (pin "1") (pinfunction "1_1") (pintype "passive"))
      (node (ref "JP3") (pin "2") (pinfunction "2_2") (pintype "passive"))
      (node (ref "JP4") (pin "GND") (pinfunction "6_GND") (pintype "passive"))
      (node (ref "JP5") (pin "4") (pinfunction "4_4") (pintype "passive"))
      (node (ref "PWR") (pin "C") (pinfunction "C_C") (pintype "passive"))
      (node (ref "R1") (pin "1") (pinfunction "1_1") (pintype "passive"))
      (node (ref "R14") (pin "2") (pinfunction "2_2") (pintype "passive"))
      (node (ref "R15") (pin "1") (pinfunction "1_1") (pintype "passive"))
      (node (ref "R21") (pin "2") (pinfunction "2_2") (pintype "passive"))
      (node (ref "R22") (pin "1") (pinfunction "1_1") (pintype "passive"))
      (node (ref "R28") (pin "2") (pinfunction "2_2") (pintype "passive"))
      (node (ref "R29") (pin "1") (pinfunction "1_1") (pintype "passive"))
      (node (ref "R35") (pin "2") (pinfunction "2_2") (pintype "passive"))
      (node (ref "R36") (pin "1") (pinfunction "1_1") (pintype "passive"))
      (node (ref "R42") (pin "2") (pinfunction "2_2") (pintype "passive"))
      (node (ref "R7") (pin "2") (pinfunction "2_2") (pintype "passive"))
      (node (ref "R8") (pin "1") (pinfunction "1_1") (pintype "passive"))
      (node (ref "U$1") (pin "6") (pinfunction "P$6_6") (pintype "bidirectional"))
      (node (ref "U$25") (pin "17") (pinfunction "GND_17") (pintype "power_in"))
      (node (ref "U$25") (pin "18") (pinfunction "GND1_18") (pintype "power_in"))
      (node (ref "U$25") (pin "2") (pinfunction "LSS_2") (pintype "power_in"))
      (node (ref "U$26") (pin "17") (pinfunction "GND_17") (pintype "power_in"))
      (node (ref "U$26") (pin "18") (pinfunction "GND1_18") (pintype "power_in"))
      (node (ref "U$26") (pin "2") (pinfunction "LSS_2") (pintype "power_in"))
      (node (ref "U$27") (pin "17") (pinfunction "GND_17") (pintype "power_in"))
      (node (ref "U$27") (pin "18") (pinfunction "GND1_18") (pintype "power_in"))
      (node (ref "U$27") (pin "2") (pinfunction "LSS_2") (pintype "power_in"))
      (node (ref "U$28") (pin "17") (pinfunction "GND_17") (pintype "power_in"))
      (node (ref "U$28") (pin "18") (pinfunction "GND1_18") (pintype "power_in"))
      (node (ref "U$28") (pin "2") (pinfunction "LSS_2") (pintype "power_in"))
      (node (ref "U$29") (pin "17") (pinfunction "GND_17") (pintype "power_in"))
      (node (ref "U$29") (pin "18") (pinfunction "GND1_18") (pintype "power_in"))
      (node (ref "U$29") (pin "2") (pinfunction "LSS_2") (pintype "power_in"))
      (node (ref "U$30") (pin "17") (pinfunction "GND_17") (pintype "power_in"))
      (node (ref "U$30") (pin "18") (pinfunction "GND1_18") (pintype "power_in"))
      (node (ref "U$30") (pin "2") (pinfunction "LSS_2") (pintype "power_in"))
      (node (ref "U$35") (pin "1") (pinfunction "1_1") (pintype "bidirectional"))
      (node (ref "U$35") (pin "2") (pinfunction "2_2") (pintype "bidirectional"))
      (node (ref "U$4") (pin "1") (pinfunction "AS_1") (pintype "bidirectional"))
      (node (ref "U$4") (pin "2") (pinfunction "GND_2") (pintype "bidirectional"))
    )
    (net (code "137") (name "Net-(ATMEGA-AREF)") (class "Default")
      (node (ref "ATMEGA") (pin "98") (pinfunction "AREF_98") (pintype "input"))
      (node (ref "C43") (pin "2") (pinfunction "2_2") (pintype "passive"))
    )
    (net (code "138") (name "Net-(C1-C1)") (class "Default")
      (node (ref "C1") (pin "1") (pinfunction "C1_1") (pintype "passive"))
      (node (ref "U$25") (pin "16") (pinfunction "CP1_16") (pintype "passive"))
    )
    (net (code "139") (name "Net-(C1-C2)") (class "Default")
      (node (ref "C1") (pin "2") (pinfunction "C2_2") (pintype "passive"))
      (node (ref "U$25") (pin "15") (pinfunction "CP2_15") (pintype "passive"))
    )
    (net (code "140") (name "Net-(C2-C2)") (class "Default")
      (node (ref "C2") (pin "2") (pinfunction "C2_2") (pintype "passive"))
      (node (ref "U$25") (pin "9") (pinfunction "CA_9") (pintype "input"))
    )
    (net (code "141") (name "Net-(C3-C2)") (class "Default")
      (node (ref "C3") (pin "2") (pinfunction "C2_2") (pintype "passive"))
      (node (ref "U$25") (pin "6") (pinfunction "CB_6") (pintype "input"))
    )
    (net (code "142") (name "Net-(C4-C1)") (class "Default")
      (node (ref "C4") (pin "1") (pinfunction "C1_1") (pintype "passive"))
      (node (ref "U$25") (pin "7") (pinfunction "VREG_7") (pintype "power_in"))
      (node (ref "U$25") (pin "8") (pinfunction "VREG1_8") (pintype "power_in"))
    )
    (net (code "143") (name "Net-(C5-C2)") (class "Default")
      (node (ref "C5") (pin "2") (pinfunction "C2_2") (pintype "passive"))
      (node (ref "R6") (pin "1") (pinfunction "1_1") (pintype "passive"))
      (node (ref "U$25") (pin "20") (pinfunction "V5_20") (pintype "output"))
    )
    (net (code "144") (name "Net-(C6-C1)") (class "Default")
      (node (ref "C6") (pin "1") (pinfunction "C1_1") (pintype "passive"))
      (node (ref "U$26") (pin "16") (pinfunction "CP1_16") (pintype "passive"))
    )
    (net (code "145") (name "Net-(C6-C2)") (class "Default")
      (node (ref "C6") (pin "2") (pinfunction "C2_2") (pintype "passive"))
      (node (ref "U$26") (pin "15") (pinfunction "CP2_15") (pintype "passive"))
    )
    (net (code "146") (name "Net-(C7-C2)") (class "Default")
      (node (ref "C7") (pin "2") (pinfunction "C2_2") (pintype "passive"))
      (node (ref "U$26") (pin "9") (pinfunction "CA_9") (pintype "input"))
    )
    (net (code "147") (name "Net-(C8-C2)") (class "Default")
      (node (ref "C8") (pin "2") (pinfunction "C2_2") (pintype "passive"))
      (node (ref "U$26") (pin "6") (pinfunction "CB_6") (pintype "input"))
    )
    (net (code "148") (name "Net-(C9-C1)") (class "Default")
      (node (ref "C9") (pin "1") (pinfunction "C1_1") (pintype "passive"))
      (node (ref "U$26") (pin "7") (pinfunction "VREG_7") (pintype "power_in"))
      (node (ref "U$26") (pin "8") (pinfunction "VREG1_8") (pintype "power_in"))
    )
    (net (code "149") (name "Net-(C10-C2)") (class "Default")
      (node (ref "C10") (pin "2") (pinfunction "C2_2") (pintype "passive"))
      (node (ref "R13") (pin "1") (pinfunction "1_1") (pintype "passive"))
      (node (ref "U$26") (pin "20") (pinfunction "V5_20") (pintype "output"))
    )
    (net (code "150") (name "Net-(C11-C1)") (class "Default")
      (node (ref "C11") (pin "1") (pinfunction "C1_1") (pintype "passive"))
      (node (ref "U$27") (pin "16") (pinfunction "CP1_16") (pintype "passive"))
    )
    (net (code "151") (name "Net-(C11-C2)") (class "Default")
      (node (ref "C11") (pin "2") (pinfunction "C2_2") (pintype "passive"))
      (node (ref "U$27") (pin "15") (pinfunction "CP2_15") (pintype "passive"))
    )
    (net (code "152") (name "Net-(C12-C2)") (class "Default")
      (node (ref "C12") (pin "2") (pinfunction "C2_2") (pintype "passive"))
      (node (ref "U$27") (pin "9") (pinfunction "CA_9") (pintype "input"))
    )
    (net (code "153") (name "Net-(C13-C2)") (class "Default")
      (node (ref "C13") (pin "2") (pinfunction "C2_2") (pintype "passive"))
      (node (ref "U$27") (pin "6") (pinfunction "CB_6") (pintype "input"))
    )
    (net (code "154") (name "Net-(C14-C1)") (class "Default")
      (node (ref "C14") (pin "1") (pinfunction "C1_1") (pintype "passive"))
      (node (ref "U$27") (pin "7") (pinfunction "VREG_7") (pintype "power_in"))
      (node (ref "U$27") (pin "8") (pinfunction "VREG1_8") (pintype "power_in"))
    )
    (net (code "155") (name "Net-(C15-C2)") (class "Default")
      (node (ref "C15") (pin "2") (pinfunction "C2_2") (pintype "passive"))
      (node (ref "R20") (pin "1") (pinfunction "1_1") (pintype "passive"))
      (node (ref "U$27") (pin "20") (pinfunction "V5_20") (pintype "output"))
    )
    (net (code "156") (name "Net-(C16-C1)") (class "Default")
      (node (ref "C16") (pin "1") (pinfunction "C1_1") (pintype "passive"))
      (node (ref "U$28") (pin "16") (pinfunction "CP1_16") (pintype "passive"))
    )
    (net (code "157") (name "Net-(C16-C2)") (class "Default")
      (node (ref "C16") (pin "2") (pinfunction "C2_2") (pintype "passive"))
      (node (ref "U$28") (pin "15") (pinfunction "CP2_15") (pintype "passive"))
    )
    (net (code "158") (name "Net-(C17-C2)") (class "Default")
      (node (ref "C17") (pin "2") (pinfunction "C2_2") (pintype "passive"))
      (node (ref "U$28") (pin "9") (pinfunction "CA_9") (pintype "input"))
    )
    (net (code "159") (name "Net-(C18-C2)") (class "Default")
      (node (ref "C18") (pin "2") (pinfunction "C2_2") (pintype "passive"))
      (node (ref "U$28") (pin "6") (pinfunction "CB_6") (pintype "input"))
    )
    (net (code "160") (name "Net-(C19-C1)") (class "Default")
      (node (ref "C19") (pin "1") (pinfunction "C1_1") (pintype "passive"))
      (node (ref "U$30") (pin "7") (pinfunction "VREG_7") (pintype "power_in"))
      (node (ref "U$30") (pin "8") (pinfunction "VREG1_8") (pintype "power_in"))
    )
    (net (code "161") (name "Net-(C20-C2)") (class "Default")
      (node (ref "C20") (pin "2") (pinfunction "C2_2") (pintype "passive"))
      (node (ref "R27") (pin "1") (pinfunction "1_1") (pintype "passive"))
      (node (ref "U$28") (pin "20") (pinfunction "V5_20") (pintype "output"))
    )
    (net (code "162") (name "Net-(C21-C1)") (class "Default")
      (node (ref "C21") (pin "1") (pinfunction "C1_1") (pintype "passive"))
      (node (ref "U$29") (pin "16") (pinfunction "CP1_16") (pintype "passive"))
    )
    (net (code "163") (name "Net-(C21-C2)") (class "Default")
      (node (ref "C21") (pin "2") (pinfunction "C2_2") (pintype "passive"))
      (node (ref "U$29") (pin "15") (pinfunction "CP2_15") (pintype "passive"))
    )
    (net (code "164") (name "Net-(C22-C2)") (class "Default")
      (node (ref "C22") (pin "2") (pinfunction "C2_2") (pintype "passive"))
      (node (ref "U$29") (pin "9") (pinfunction "CA_9") (pintype "input"))
    )
    (net (code "165") (name "Net-(C23-C2)") (class "Default")
      (node (ref "C23") (pin "2") (pinfunction "C2_2") (pintype "passive"))
      (node (ref "U$29") (pin "6") (pinfunction "CB_6") (pintype "input"))
    )
    (net (code "166") (name "Net-(C24-C1)") (class "Default")
      (node (ref "C24") (pin "1") (pinfunction "C1_1") (pintype "passive"))
      (node (ref "U$29") (pin "7") (pinfunction "VREG_7") (pintype "power_in"))
      (node (ref "U$29") (pin "8") (pinfunction "VREG1_8") (pintype "power_in"))
    )
    (net (code "167") (name "Net-(C25-C2)") (class "Default")
      (node (ref "C25") (pin "2") (pinfunction "C2_2") (pintype "passive"))
      (node (ref "R34") (pin "1") (pinfunction "1_1") (pintype "passive"))
      (node (ref "U$29") (pin "20") (pinfunction "V5_20") (pintype "output"))
    )
    (net (code "168") (name "Net-(C26-C1)") (class "Default")
      (node (ref "C26") (pin "1") (pinfunction "C1_1") (pintype "passive"))
      (node (ref "U$30") (pin "16") (pinfunction "CP1_16") (pintype "passive"))
    )
    (net (code "169") (name "Net-(C26-C2)") (class "Default")
      (node (ref "C26") (pin "2") (pinfunction "C2_2") (pintype "passive"))
      (node (ref "U$30") (pin "15") (pinfunction "CP2_15") (pintype "passive"))
    )
    (net (code "170") (name "Net-(C27-C2)") (class "Default")
      (node (ref "C27") (pin "2") (pinfunction "C2_2") (pintype "passive"))
      (node (ref "U$30") (pin "9") (pinfunction "CA_9") (pintype "input"))
    )
    (net (code "171") (name "Net-(C28-C2)") (class "Default")
      (node (ref "C28") (pin "2") (pinfunction "C2_2") (pintype "passive"))
      (node (ref "U$30") (pin "6") (pinfunction "CB_6") (pintype "input"))
    )
    (net (code "172") (name "Net-(C29-C1)") (class "Default")
      (node (ref "C29") (pin "1") (pinfunction "C1_1") (pintype "passive"))
      (node (ref "U$28") (pin "7") (pinfunction "VREG_7") (pintype "power_in"))
      (node (ref "U$28") (pin "8") (pinfunction "VREG1_8") (pintype "power_in"))
    )
    (net (code "173") (name "Net-(C30-C2)") (class "Default")
      (node (ref "C30") (pin "2") (pinfunction "C2_2") (pintype "passive"))
      (node (ref "R41") (pin "1") (pinfunction "1_1") (pintype "passive"))
      (node (ref "U$30") (pin "20") (pinfunction "V5_20") (pintype "output"))
    )
    (net (code "174") (name "Net-(DC-DC-~{ERROR})") (class "Default")
      (node (ref "DC-DC") (pin "17") (pinfunction "~{ERROR}_17") (pintype "input"))
      (node (ref "R79") (pin "2") (pinfunction "2_2") (pintype "passive"))
    )
    (net (code "175") (name "Net-(INT-PadA)") (class "Default")
      (node (ref "INT") (pin "A") (pinfunction "A_A") (pintype "passive"))
      (node (ref "R77") (pin "2") (pinfunction "2_2") (pintype "passive"))
    )
    (net (code "176") (name "Net-(PWR-PadA)") (class "Default")
      (node (ref "PWR") (pin "A") (pinfunction "A_A") (pintype "passive"))
      (node (ref "R74") (pin "2") (pinfunction "2_2") (pintype "passive"))
    )
    (net (code "177") (name "Net-(R69-Pad1)") (class "Default")
      (node (ref "R69") (pin "1") (pinfunction "1_1") (pintype "passive"))
      (node (ref "RX0") (pin "C") (pinfunction "C_C") (pintype "passive"))
    )
    (net (code "178") (name "Net-(R70-Pad1)") (class "Default")
      (node (ref "R70") (pin "1") (pinfunction "1_1") (pintype "passive"))
      (node (ref "TX0") (pin "C") (pinfunction "C_C") (pintype "passive"))
    )
    (net (code "179") (name "Net-(R75-Pad2)") (class "Default")
      (node (ref "R75") (pin "2") (pinfunction "2_2") (pintype "passive"))
      (node (ref "TX-CAN") (pin "A") (pinfunction "A_A") (pintype "passive"))
    )
    (net (code "180") (name "Net-(R76-Pad2)") (class "Default")
      (node (ref "R76") (pin "2") (pinfunction "2_2") (pintype "passive"))
      (node (ref "RX-CAN") (pin "A") (pinfunction "A_A") (pintype "passive"))
    )
    (net (code "181") (name "Net-(U$25-RDEAD)") (class "Default")
      (node (ref "R1") (pin "2") (pinfunction "2_2") (pintype "passive"))
      (node (ref "U$25") (pin "27") (pinfunction "RDEAD_27") (pintype "power_in"))
    )
    (net (code "182") (name "Net-(U$25-VDSTH)") (class "Default")
      (node (ref "R6") (pin "2") (pinfunction "2_2") (pintype "passive"))
      (node (ref "R7") (pin "1") (pinfunction "1_1") (pintype "passive"))
      (node (ref "U$25") (pin "28") (pinfunction "VDSTH_28") (pintype "input"))
    )
    (net (code "183") (name "Net-(U$26-RDEAD)") (class "Default")
      (node (ref "R8") (pin "2") (pinfunction "2_2") (pintype "passive"))
      (node (ref "U$26") (pin "27") (pinfunction "RDEAD_27") (pintype "power_in"))
    )
    (net (code "184") (name "Net-(U$26-VDSTH)") (class "Default")
      (node (ref "R13") (pin "2") (pinfunction "2_2") (pintype "passive"))
      (node (ref "R14") (pin "1") (pinfunction "1_1") (pintype "passive"))
      (node (ref "U$26") (pin "28") (pinfunction "VDSTH_28") (pintype "input"))
    )
    (net (code "185") (name "Net-(U$27-RDEAD)") (class "Default")
      (node (ref "R15") (pin "2") (pinfunction "2_2") (pintype "passive"))
      (node (ref "U$27") (pin "27") (pinfunction "RDEAD_27") (pintype "power_in"))
    )
    (net (code "186") (name "Net-(U$27-VDSTH)") (class "Default")
      (node (ref "R20") (pin "2") (pinfunction "2_2") (pintype "passive"))
      (node (ref "R21") (pin "1") (pinfunction "1_1") (pintype "passive"))
      (node (ref "U$27") (pin "28") (pinfunction "VDSTH_28") (pintype "input"))
    )
    (net (code "187") (name "Net-(U$28-RDEAD)") (class "Default")
      (node (ref "R22") (pin "2") (pinfunction "2_2") (pintype "passive"))
      (node (ref "U$28") (pin "27") (pinfunction "RDEAD_27") (pintype "power_in"))
    )
    (net (code "188") (name "Net-(U$28-VDSTH)") (class "Default")
      (node (ref "R27") (pin "2") (pinfunction "2_2") (pintype "passive"))
      (node (ref "R28") (pin "1") (pinfunction "1_1") (pintype "passive"))
      (node (ref "U$28") (pin "28") (pinfunction "VDSTH_28") (pintype "input"))
    )
    (net (code "189") (name "Net-(U$29-RDEAD)") (class "Default")
      (node (ref "R29") (pin "2") (pinfunction "2_2") (pintype "passive"))
      (node (ref "U$29") (pin "27") (pinfunction "RDEAD_27") (pintype "power_in"))
    )
    (net (code "190") (name "Net-(U$29-VDSTH)") (class "Default")
      (node (ref "R34") (pin "2") (pinfunction "2_2") (pintype "passive"))
      (node (ref "R35") (pin "1") (pinfunction "1_1") (pintype "passive"))
      (node (ref "U$29") (pin "28") (pinfunction "VDSTH_28") (pintype "input"))
    )
    (net (code "191") (name "Net-(U$30-RDEAD)") (class "Default")
      (node (ref "R36") (pin "2") (pinfunction "2_2") (pintype "passive"))
      (node (ref "U$30") (pin "27") (pinfunction "RDEAD_27") (pintype "power_in"))
    )
    (net (code "192") (name "Net-(U$30-VDSTH)") (class "Default")
      (node (ref "R41") (pin "2") (pinfunction "2_2") (pintype "passive"))
      (node (ref "R42") (pin "1") (pinfunction "1_1") (pintype "passive"))
      (node (ref "U$30") (pin "28") (pinfunction "VDSTH_28") (pintype "input"))
    )
    (net (code "193") (name "unconnected-(ATMEGA-(ICP4)_PL0-Pad35)") (class "Default")
      (node (ref "ATMEGA") (pin "35") (pinfunction "(ICP4)_PL0_35") (pintype "bidirectional"))
    )
    (net (code "194") (name "unconnected-(ATMEGA-(ICP5)_PL1-Pad36)") (class "Default")
      (node (ref "ATMEGA") (pin "36") (pinfunction "(ICP5)_PL1_36") (pintype "bidirectional"))
    )
    (net (code "195") (name "unconnected-(ATMEGA-(T0)_PD7-Pad50)") (class "Default")
      (node (ref "ATMEGA") (pin "50") (pinfunction "(T0)_PD7_50") (pintype "bidirectional"))
    )
    (net (code "196") (name "unconnected-(ATMEGA-(T1)_PD6-Pad49)") (class "Default")
      (node (ref "ATMEGA") (pin "49") (pinfunction "(T1)_PD6_49") (pintype "bidirectional"))
    )
    (net (code "197") (name "unconnected-(ATMEGA-(XCK1)_PD5-Pad48)") (class "Default")
      (node (ref "ATMEGA") (pin "48") (pinfunction "(XCK1)_PD5_48") (pintype "bidirectional"))
    )
    (net (code "198") (name "unconnected-(ATMEGA-PA5_(AD5)-Pad73)") (class "Default")
      (node (ref "ATMEGA") (pin "73") (pinfunction "PA5_(AD5)_73") (pintype "bidirectional"))
    )
    (net (code "199") (name "unconnected-(ATMEGA-PC5_(A13)-Pad58)") (class "Default")
      (node (ref "ATMEGA") (pin "58") (pinfunction "PC5_(A13)_58") (pintype "bidirectional"))
    )
    (net (code "200") (name "unconnected-(ATMEGA-PF5_(ADC5{slash}TMS)-Pad92)") (class "Default")
      (node (ref "ATMEGA") (pin "92") (pinfunction "PF5_(ADC5/TMS)_92") (pintype "bidirectional"))
    )
    (net (code "201") (name "unconnected-(CAN-CONTROLLER-~{TX0RTS}-Pad4)") (class "Default")
      (node (ref "CAN-CONTROLLER") (pin "4") (pinfunction "~{TX0RTS}_4") (pintype "input"))
    )
    (net (code "202") (name "unconnected-(CAN-CONTROLLER-~{TX1RTS}-Pad5)") (class "Default")
      (node (ref "CAN-CONTROLLER") (pin "5") (pinfunction "~{TX1RTS}_5") (pintype "input"))
    )
    (net (code "203") (name "unconnected-(CAN-CONTROLLER-~{TX2RTS}-Pad6)") (class "Default")
      (node (ref "CAN-CONTROLLER") (pin "6") (pinfunction "~{TX2RTS}_6") (pintype "input"))
    )
    (net (code "204") (name "unconnected-(DC-DC-DNC-Pad15)") (class "Default")
      (node (ref "DC-DC") (pin "15") (pinfunction "DNC_15") (pintype "no_connect"))
    )
    (net (code "205") (name "unconnected-(DC-DC-NC-Pad3)") (class "Default")
      (node (ref "DC-DC") (pin "3") (pinfunction "NC_3") (pintype "no_connect"))
    )
    (net (code "206") (name "unconnected-(DC-DC-SYNC-Pad28)") (class "Default")
      (node (ref "DC-DC") (pin "28") (pinfunction "SYNC_28") (pintype "input"))
    )
    (net (code "207") (name "unconnected-(JP3-Pad3)") (class "Default")
      (node (ref "JP3") (pin "3") (pinfunction "3_3") (pintype "passive"))
    )
    (net (code "208") (name "unconnected-(JP3-Pad4)") (class "Default")
      (node (ref "JP3") (pin "4") (pinfunction "4_4") (pintype "passive"))
    )
    (net (code "209") (name "unconnected-(JP4-5-PadCTS)") (class "Default")
      (node (ref "JP4") (pin "CTS") (pinfunction "5_CTS") (pintype "passive"))
    )
    (net (code "210") (name "unconnected-(U$4-ALRT-Pad5)") (class "Default")
      (node (ref "U$4") (pin "5") (pinfunction "ALRT_5") (pintype "bidirectional"))
    )
  )
)
